# MicroRC-C.net
KiCad netlist of a schematic drawn in EAGLE
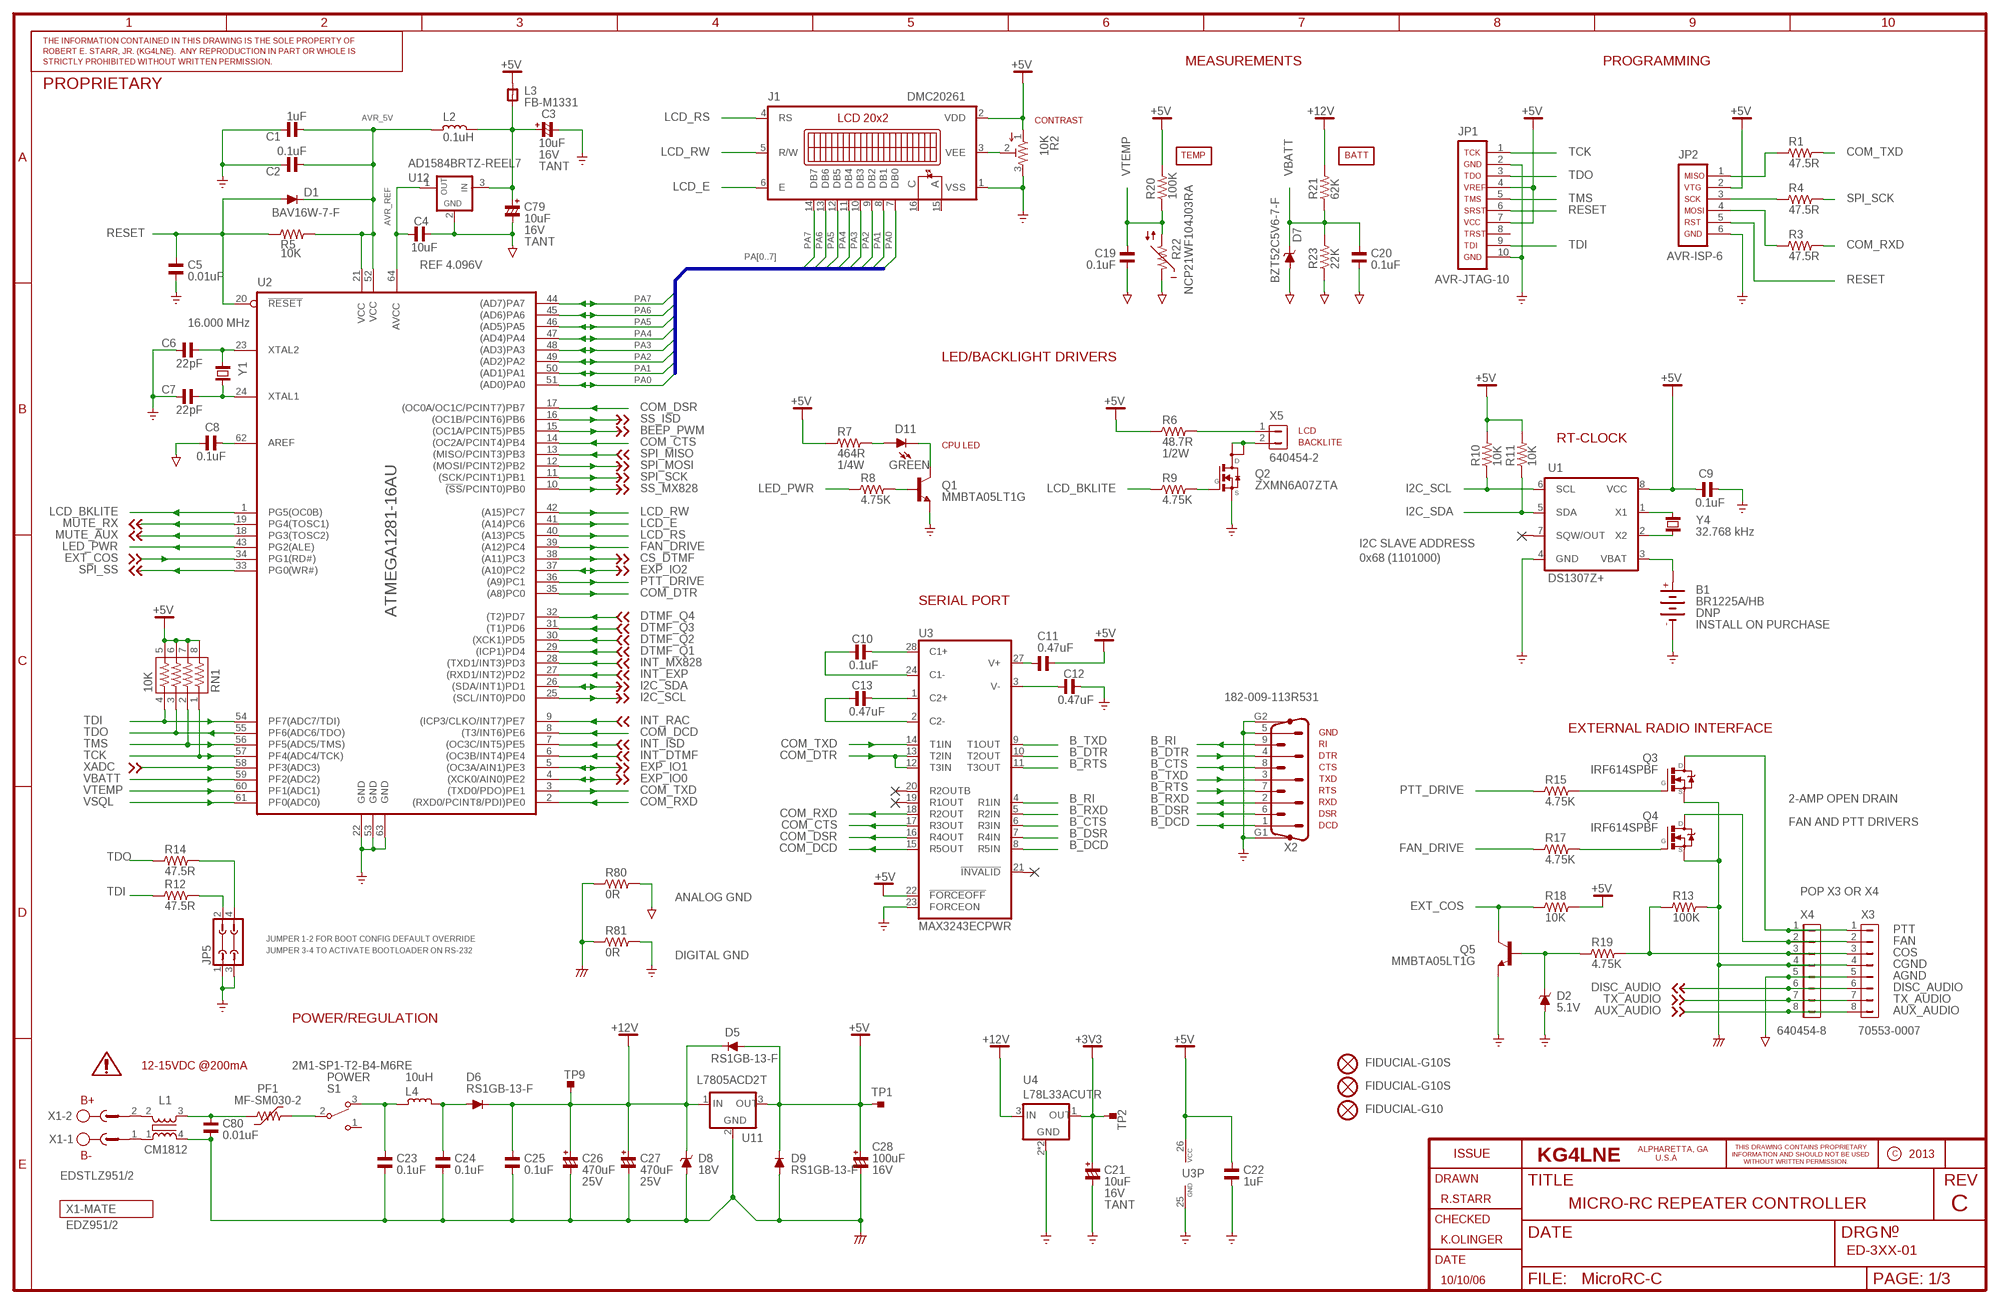
[diagram p0: schematic, sheet 1]
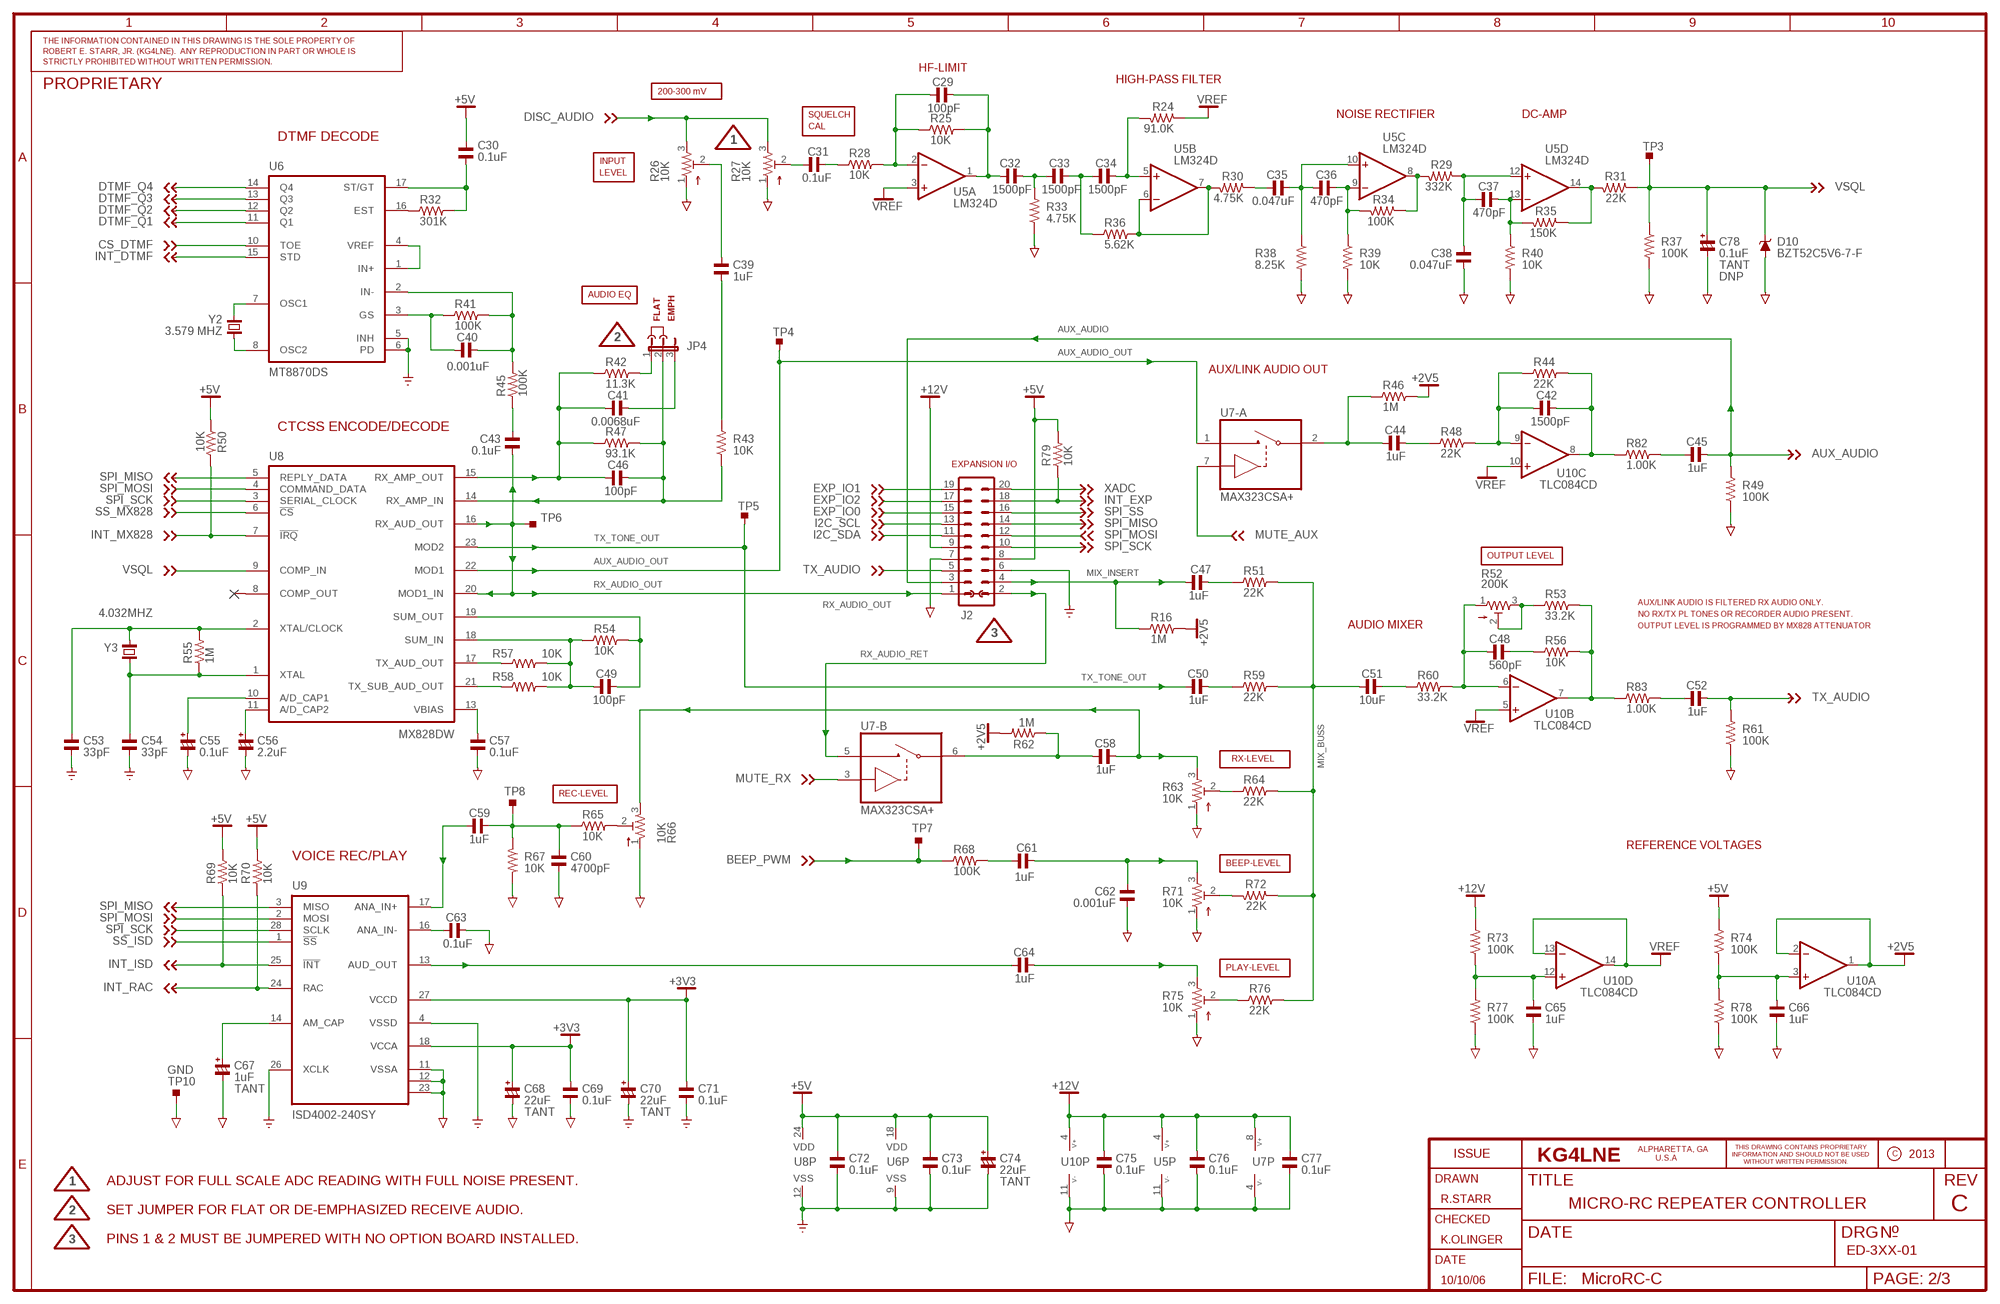
[diagram p1: schematic, sheet 2]
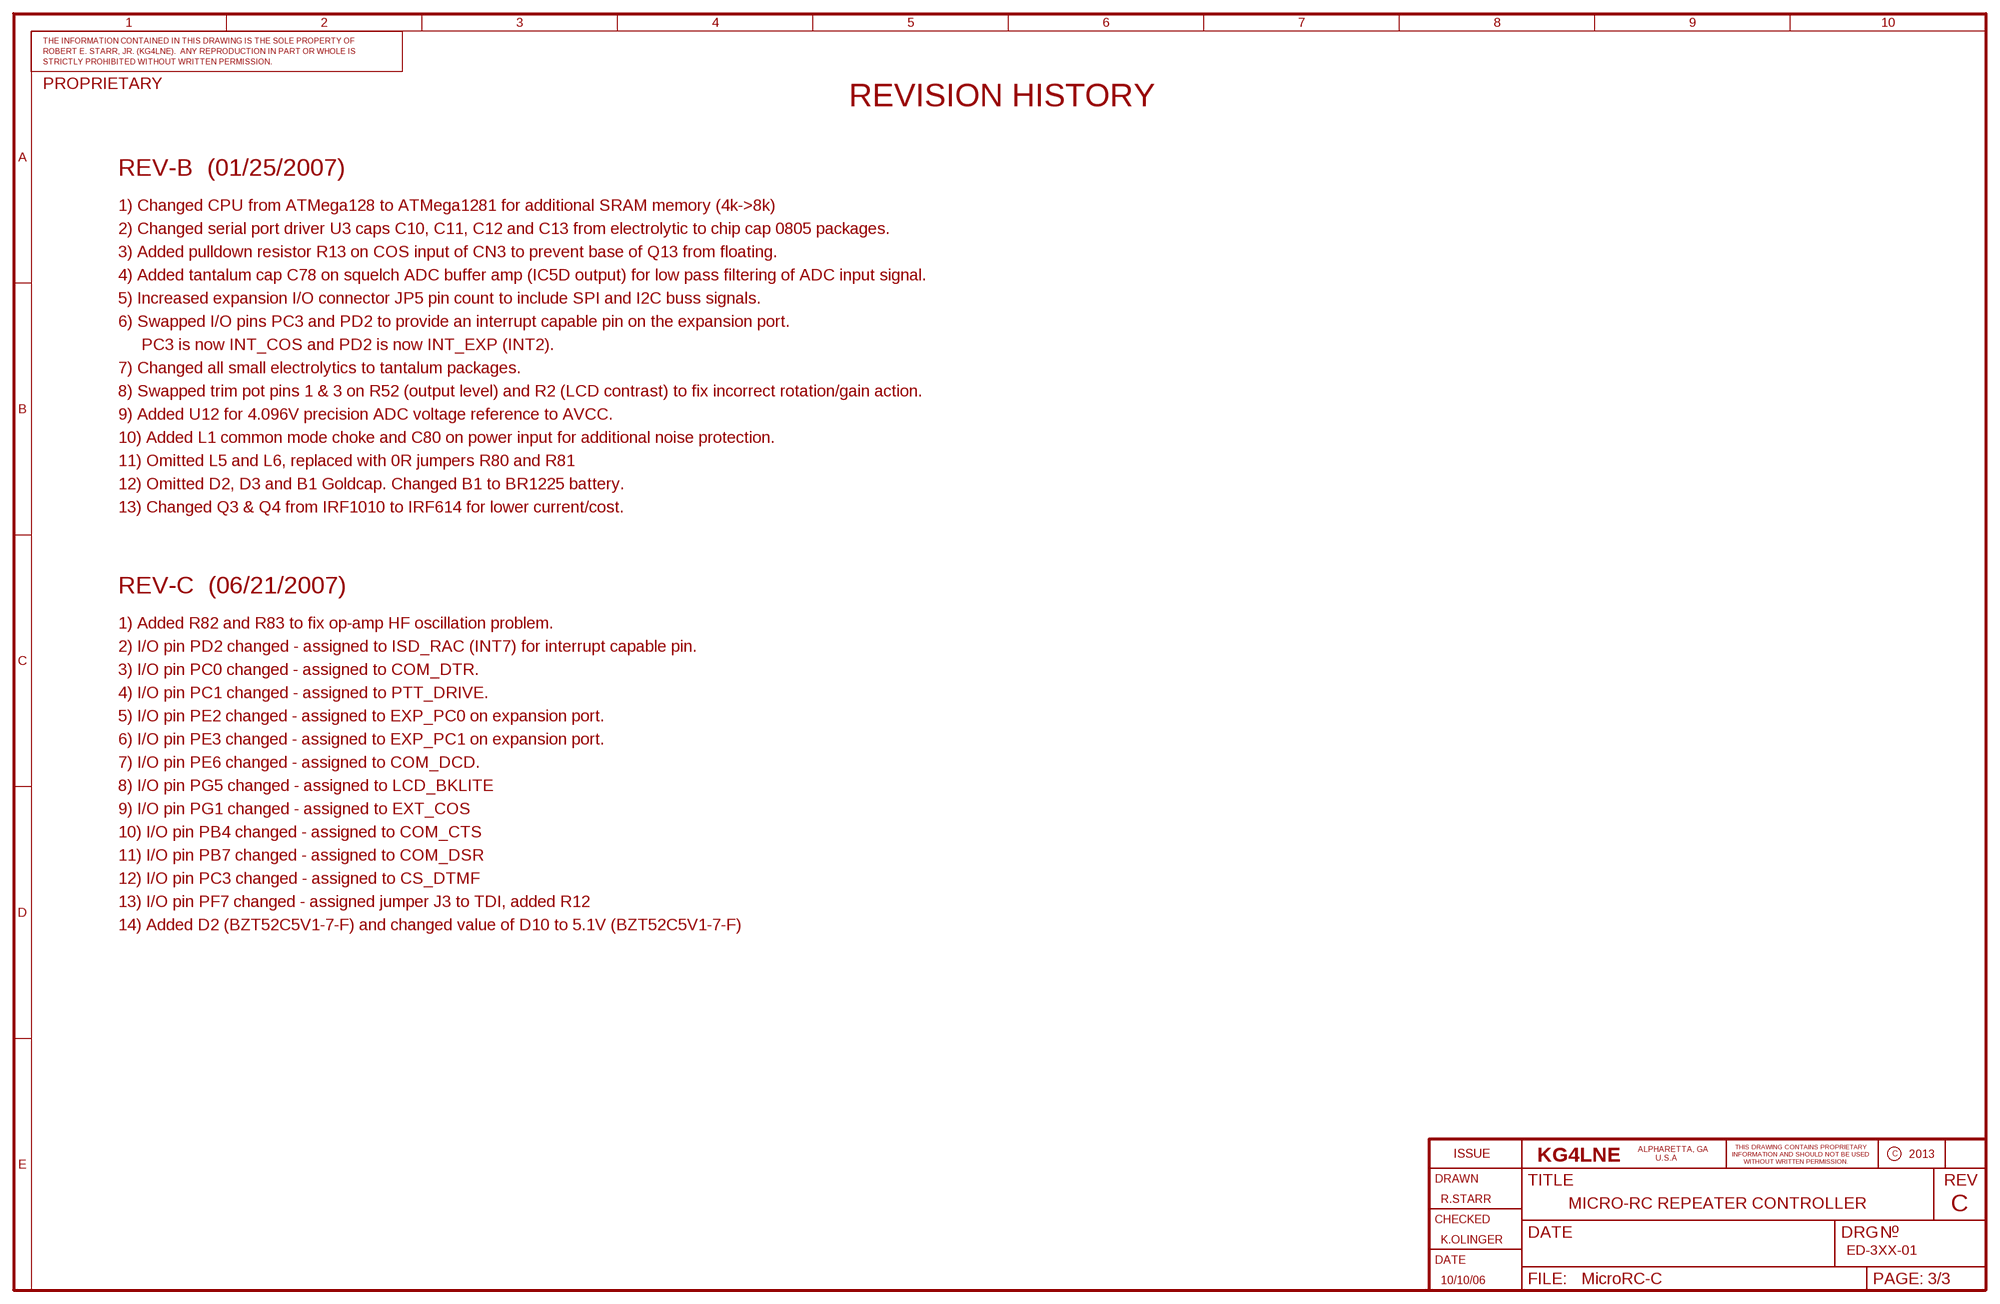
[diagram p2: schematic, sheet 3]

(export (version "E")
  (design (tool "Eeschema 10.0.6"))
  (components
    (comp (ref "B1")
      (value "BR1225A/HB")
      (footprint "eagle-import:BR1225")
      (fields (field (name "PLACE") "INSTALL ON PURCHASE"))
      (libsource (lib "eagle-import") (part "BR1225"))
    )
    (comp (ref "C1")
      (value "1uF")
      (footprint "eagle-import:C0805")
      (fields (field (name "PARTNO") "C0805C105Z3VACTU"))
      (libsource (lib "eagle-import") (part "C_0805"))
    )
    (comp (ref "C2")
      (value "0.1uF")
      (footprint "eagle-import:C0805")
      (fields (field (name "PARTNO") "C0805F104K5RACTU"))
      (libsource (lib "eagle-import") (part "C_0805"))
    )
    (comp (ref "C3")
      (value "10uF")
      (footprint "eagle-import:C3528_T")
      (fields
        (field (name "PARTNO") "T491B106M016AT")
        (field (name "TYPE") "TANT")
        (field (name "VOLT") "16V")
      )
      (libsource (lib "eagle-import") (part "CP_3528"))
    )
    (comp (ref "C4")
      (value "10uF")
      (footprint "eagle-import:C0805")
      (fields (field (name "PARTNO") "C0805C106K9PACTU"))
      (libsource (lib "eagle-import") (part "C_0805"))
    )
    (comp (ref "C5")
      (value "0.01uF")
      (footprint "eagle-import:C0805")
      (fields (field (name "PARTNO") "C0805C103K5RACTU"))
      (libsource (lib "eagle-import") (part "C_0805"))
    )
    (comp (ref "C6")
      (value "22pF")
      (footprint "eagle-import:C0805")
      (fields (field (name "PARTNO") "C0805C220J5GACTU"))
      (libsource (lib "eagle-import") (part "C_0805"))
    )
    (comp (ref "C7")
      (value "22pF")
      (footprint "eagle-import:C0805")
      (fields (field (name "PARTNO") "C0805C220J5GACTU"))
      (libsource (lib "eagle-import") (part "C_0805"))
    )
    (comp (ref "C8")
      (value "0.1uF")
      (footprint "eagle-import:C0805")
      (fields (field (name "PARTNO") "C0805F104K5RACTU"))
      (libsource (lib "eagle-import") (part "C_0805"))
    )
    (comp (ref "C9")
      (value "0.1uF")
      (footprint "eagle-import:C0805")
      (fields (field (name "PARTNO") "C0805F104K5RACTU"))
      (libsource (lib "eagle-import") (part "C_0805"))
    )
    (comp (ref "C10")
      (value "0.1uF")
      (footprint "eagle-import:C0805")
      (fields (field (name "PARTNO") "C0805F104K5RACTU"))
      (libsource (lib "eagle-import") (part "C_0805"))
    )
    (comp (ref "C11")
      (value "0.47uF")
      (footprint "eagle-import:C0805")
      (fields (field (name "PARTNO") "C0805F474K3RACTU"))
      (libsource (lib "eagle-import") (part "C_0805"))
    )
    (comp (ref "C12")
      (value "0.47uF")
      (footprint "eagle-import:C0805")
      (fields (field (name "PARTNO") "C0805F474K3RACTU"))
      (libsource (lib "eagle-import") (part "C_0805"))
    )
    (comp (ref "C13")
      (value "0.47uF")
      (footprint "eagle-import:C0805")
      (fields (field (name "PARTNO") "C0805F474K3RACTU"))
      (libsource (lib "eagle-import") (part "C_0805"))
    )
    (comp (ref "C19")
      (value "0.1uF")
      (footprint "eagle-import:C0805")
      (fields (field (name "PARTNO") "C0805F104K5RACTU"))
      (libsource (lib "eagle-import") (part "C_0805"))
    )
    (comp (ref "C20")
      (value "0.1uF")
      (footprint "eagle-import:C0805")
      (fields (field (name "PARTNO") "C0805F104K5RACTU"))
      (libsource (lib "eagle-import") (part "C_0805"))
    )
    (comp (ref "C21")
      (value "10uF")
      (footprint "eagle-import:C3528_T")
      (fields
        (field (name "PARTNO") "T491B106M016AT")
        (field (name "TYPE") "TANT")
        (field (name "VOLT") "16V")
      )
      (libsource (lib "eagle-import") (part "CP_3528"))
    )
    (comp (ref "C22")
      (value "1uF")
      (footprint "eagle-import:C0805")
      (fields (field (name "PARTNO") "C0805C105Z3VACTU"))
      (libsource (lib "eagle-import") (part "C_0805"))
    )
    (comp (ref "C23")
      (value "0.1uF")
      (footprint "eagle-import:C1206")
      (fields (field (name "PARTNO") "C1206C104K5RACTU"))
      (libsource (lib "eagle-import") (part "C_1206"))
    )
    (comp (ref "C24")
      (value "0.1uF")
      (footprint "eagle-import:C1206")
      (fields (field (name "PARTNO") "C1206C104K5RACTU"))
      (libsource (lib "eagle-import") (part "C_1206"))
    )
    (comp (ref "C25")
      (value "0.1uF")
      (footprint "eagle-import:C1206")
      (fields (field (name "PARTNO") "C1206C104K5RACTU"))
      (libsource (lib "eagle-import") (part "C_1206"))
    )
    (comp (ref "C26")
      (value "470uF")
      (footprint "eagle-import:CSV-G")
      (fields (field (name "PARTNO") "EEE-1EA471P") (field (name "VOLT") "25V"))
      (libsource (lib "eagle-import") (part "CP_SV-G"))
    )
    (comp (ref "C27")
      (value "470uF")
      (footprint "eagle-import:CSV-G")
      (fields (field (name "PARTNO") "EEE-1EA471P") (field (name "VOLT") "25V"))
      (libsource (lib "eagle-import") (part "CP_SV-G"))
    )
    (comp (ref "C28")
      (value "100uF")
      (footprint "eagle-import:CSV-E_F")
      (fields (field (name "PARTNO") "EEE-1CA101P") (field (name "VOLT") "16V"))
      (libsource (lib "eagle-import") (part "CP_SV-E/F"))
    )
    (comp (ref "C79")
      (value "10uF")
      (footprint "eagle-import:C3528_T")
      (fields
        (field (name "PARTNO") "T491B106M016AT")
        (field (name "TYPE") "TANT")
        (field (name "VOLT") "16V")
      )
      (libsource (lib "eagle-import") (part "CP_3528"))
    )
    (comp (ref "C80")
      (value "0.01uF")
      (footprint "eagle-import:C1206")
      (fields (field (name "PARTNO") "12065C103KAT2A"))
      (libsource (lib "eagle-import") (part "C_1206"))
    )
    (comp (ref "D1")
      (value "BAV16W-7-F")
      (footprint "eagle-import:SOD123")
      (libsource (lib "eagle-import") (part "DIODE-SOD123"))
    )
    (comp (ref "D2")
      (value "5.1V")
      (footprint "eagle-import:SOD123")
      (fields (field (name "PARTNO") "BZT52C5V1-7-F"))
      (libsource (lib "eagle-import") (part "ZENER-DIODESOD123"))
    )
    (comp (ref "D5")
      (value "RS1GB-13-F")
      (footprint "eagle-import:SMB")
      (libsource (lib "eagle-import") (part "S1GB-13"))
    )
    (comp (ref "D6")
      (value "RS1GB-13-F")
      (footprint "eagle-import:SMB")
      (libsource (lib "eagle-import") (part "S1GB-13"))
    )
    (comp (ref "D7")
      (value "BZT52C5V6-7-F")
      (footprint "eagle-import:SOD123")
      (libsource (lib "eagle-import") (part "ZENER-DIODESOD123"))
    )
    (comp (ref "D8")
      (value "18V")
      (footprint "eagle-import:SMB")
      (fields (field (name "PARTNO") "1SMB5931BT3G"))
      (libsource (lib "eagle-import") (part "ZENER-DIODESMB"))
    )
    (comp (ref "D9")
      (value "RS1GB-13-F")
      (footprint "eagle-import:SMB")
      (libsource (lib "eagle-import") (part "S1GB-13"))
    )
    (comp (ref "D11")
      (value "GREEN")
      (footprint "eagle-import:LED535")
      (fields (field (name "PARTNO") "5350T5"))
      (libsource (lib "eagle-import") (part "LED535XX"))
    )
    (comp (ref "FIDUCIAL1")
      (value "FIDUCIAL-G10S")
      (footprint "eagle-import:G10S")
      (libsource (lib "eagle-import") (part "FIDUCIAL-G10S"))
    )
    (comp (ref "FIDUCIAL2")
      (value "FIDUCIAL-G10S")
      (footprint "eagle-import:G10S")
      (libsource (lib "eagle-import") (part "FIDUCIAL-G10S"))
    )
    (comp (ref "FIDUCIAL3")
      (value "FIDUCIAL-G10")
      (footprint "eagle-import:G10")
      (libsource (lib "eagle-import") (part "FIDUCIAL-G10"))
    )
    (comp (ref "J1")
      (value "DMC20261")
      (footprint "eagle-import:DMC20261")
      (libsource (lib "eagle-import") (part "DMC20261"))
    )
    (comp (ref "JP1")
      (value "AVR-JTAG-10")
      (footprint "eagle-import:AVR-JTAG-10")
      (libsource (lib "eagle-import") (part "AVR-JTAG-10"))
    )
    (comp (ref "JP2")
      (value "AVR-ISP-6")
      (footprint "eagle-import:AVR-ISP-6")
      (libsource (lib "eagle-import") (part "AVR-ISP-6"))
    )
    (comp (ref "JP5")
      (value "JP2Q")
      (footprint "eagle-import:JP2Q")
      (libsource (lib "eagle-import") (part "JP2Q"))
    )
    (comp (ref "L1")
      (value "CM1812")
      (footprint "eagle-import:CM1812")
      (fields (field (name "PARTNO") "CM1812R600R-10"))
      (libsource (lib "eagle-import") (part "CM1812"))
    )
    (comp (ref "L2")
      (value "0.1uH")
      (footprint "eagle-import:L1206")
      (fields (field (name "PARTNO") "PM1210-R10J"))
      (libsource (lib "eagle-import") (part "L_1206"))
    )
    (comp (ref "L3")
      (value "FB-M1331")
      (footprint "eagle-import:L1206")
      (fields (field (name "PARTNO") "PM2001-200"))
      (libsource (lib "eagle-import") (part "FB_1206"))
    )
    (comp (ref "L4")
      (value "10uH")
      (footprint "eagle-import:PM-13")
      (fields (field (name "PARTNO") "PM3308-100M"))
      (libsource (lib "eagle-import") (part "L-PM3308"))
    )
    (comp (ref "PF1")
      (value "MF-SM030-2")
      (footprint "eagle-import:SMD-7555")
      (libsource (lib "eagle-import") (part "POLYSWITCH-SMD-7555"))
    )
    (comp (ref "Q1")
      (value "MMBTA05LT1G")
      (footprint "eagle-import:SOT23")
      (libsource (lib "eagle-import") (part "MMBTA05LT1"))
    )
    (comp (ref "Q2")
      (value "ZXMN6A07ZTA")
      (footprint "eagle-import:SOT89")
      (libsource (lib "eagle-import") (part "ZXMN6A07Z"))
    )
    (comp (ref "Q3")
      (value "IRF614SPBF")
      (footprint "eagle-import:D2PAK")
      (libsource (lib "eagle-import") (part "IRF614"))
    )
    (comp (ref "Q4")
      (value "IRF614SPBF")
      (footprint "eagle-import:D2PAK")
      (libsource (lib "eagle-import") (part "IRF614"))
    )
    (comp (ref "Q5")
      (value "MMBTA05LT1G")
      (footprint "eagle-import:SOT23")
      (libsource (lib "eagle-import") (part "MMBTA05LT1"))
    )
    (comp (ref "R1")
      (value "47.5R")
      (footprint "eagle-import:R0805")
      (fields (field (name "PARTNO") "ERJ-6ENF47R5V"))
      (libsource (lib "eagle-import") (part "R_0805"))
    )
    (comp (ref "R2")
      (value "10K")
      (footprint "eagle-import:EVM-L4G")
      (fields (field (name "PARTNO") "EVM-L4GA00B14"))
      (libsource (lib "eagle-import") (part "TRIM_EU-EVM-L4G"))
    )
    (comp (ref "R3")
      (value "47.5R")
      (footprint "eagle-import:R0805")
      (fields (field (name "PARTNO") "ERJ-6ENF47R5V"))
      (libsource (lib "eagle-import") (part "R_0805"))
    )
    (comp (ref "R4")
      (value "47.5R")
      (footprint "eagle-import:R0805")
      (fields (field (name "PARTNO") "ERJ-6ENF47R5V"))
      (libsource (lib "eagle-import") (part "R_0805"))
    )
    (comp (ref "R5")
      (value "10K")
      (footprint "eagle-import:R0805")
      (fields (field (name "PARTNO") "ERJ-6ENF1002V"))
      (libsource (lib "eagle-import") (part "R_0805"))
    )
    (comp (ref "R6")
      (value "48.7R")
      (footprint "eagle-import:R2010")
      (fields (field (name "PARTNO") "ERJ-12SF48R7U") (field (name "RATE") "1/2W"))
      (libsource (lib "eagle-import") (part "R_2010"))
    )
    (comp (ref "R7")
      (value "464R")
      (footprint "eagle-import:R1210")
      (fields (field (name "PARTNO") "ERJ-14NF4640U") (field (name "RATE") "1/4W"))
      (libsource (lib "eagle-import") (part "R_1210"))
    )
    (comp (ref "R8")
      (value "4.75K")
      (footprint "eagle-import:R0805")
      (fields (field (name "PARTNO") "ERJ-6ENF4751V"))
      (libsource (lib "eagle-import") (part "R_0805"))
    )
    (comp (ref "R9")
      (value "4.75K")
      (footprint "eagle-import:R0805")
      (fields (field (name "PARTNO") "ERJ-6ENF4751V"))
      (libsource (lib "eagle-import") (part "R_0805"))
    )
    (comp (ref "R10")
      (value "10K")
      (footprint "eagle-import:R0805")
      (fields (field (name "PARTNO") "ERJ-6ENF1002V"))
      (libsource (lib "eagle-import") (part "R_0805"))
    )
    (comp (ref "R11")
      (value "10K")
      (footprint "eagle-import:R0805")
      (fields (field (name "PARTNO") "ERJ-6ENF1002V"))
      (libsource (lib "eagle-import") (part "R_0805"))
    )
    (comp (ref "R12")
      (value "47.5R")
      (footprint "eagle-import:R0805")
      (fields (field (name "PARTNO") "ERJ-6ENF47R5V"))
      (libsource (lib "eagle-import") (part "R_0805"))
    )
    (comp (ref "R13")
      (value "100K")
      (footprint "eagle-import:R0805")
      (fields (field (name "PARTNO") "ERJ-6ENF1003V"))
      (libsource (lib "eagle-import") (part "R_0805"))
    )
    (comp (ref "R14")
      (value "47.5R")
      (footprint "eagle-import:R0805")
      (fields (field (name "PARTNO") "ERJ-6ENF47R5V"))
      (libsource (lib "eagle-import") (part "R_0805"))
    )
    (comp (ref "R15")
      (value "4.75K")
      (footprint "eagle-import:R0805")
      (fields (field (name "PARTNO") "ERJ-6ENF4751V"))
      (libsource (lib "eagle-import") (part "R_0805"))
    )
    (comp (ref "R17")
      (value "4.75K")
      (footprint "eagle-import:R0805")
      (fields (field (name "PARTNO") "ERJ-6ENF4751V"))
      (libsource (lib "eagle-import") (part "R_0805"))
    )
    (comp (ref "R18")
      (value "10K")
      (footprint "eagle-import:R0805")
      (fields (field (name "PARTNO") "ERJ-6ENF1002V"))
      (libsource (lib "eagle-import") (part "R_0805"))
    )
    (comp (ref "R19")
      (value "4.75K")
      (footprint "eagle-import:R0805")
      (fields (field (name "PARTNO") "ERJ-6ENF4751V"))
      (libsource (lib "eagle-import") (part "R_0805"))
    )
    (comp (ref "R20")
      (value "100K")
      (footprint "eagle-import:R0805")
      (fields (field (name "PARTNO") "ERJ-6ENF1003V"))
      (libsource (lib "eagle-import") (part "R_0805"))
    )
    (comp (ref "R21")
      (value "62K")
      (footprint "eagle-import:R0805")
      (fields (field (name "PARTNO") "ERJ-6ENF6192V"))
      (libsource (lib "eagle-import") (part "R_0805"))
    )
    (comp (ref "R22")
      (value "NCP21WF104J03RA")
      (footprint "eagle-import:R0805")
      (libsource (lib "eagle-import") (part "NCP-0805"))
    )
    (comp (ref "R23")
      (value "22K")
      (footprint "eagle-import:R0805")
      (fields (field (name "PARTNO") "ERJ-6ENF2212V"))
      (libsource (lib "eagle-import") (part "R_0805"))
    )
    (comp (ref "R80")
      (value "0R")
      (footprint "eagle-import:R0805")
      (fields (field (name "PARTNO") "RC0805JR-070RL"))
      (libsource (lib "eagle-import") (part "R_0805"))
    )
    (comp (ref "R81")
      (value "0R")
      (footprint "eagle-import:R0805")
      (fields (field (name "PARTNO") "RC0805JR-070RL"))
      (libsource (lib "eagle-import") (part "R_0805"))
    )
    (comp (ref "RN1")
      (value "10K")
      (footprint "eagle-import:744-8")
      (fields (field (name "PARTNO") "744C083103JPTR"))
      (libsource (lib "eagle-import") (part "744-8"))
    )
    (comp (ref "S1")
      (value "2M1-SP1-T2-B4-M6RE")
      (footprint "eagle-import:CK-A")
      (libsource (lib "eagle-import") (part "CK-A"))
    )
    (comp (ref "TP1")
      (value "TPTP10SQ")
      (footprint "eagle-import:TP10SQ")
      (libsource (lib "eagle-import") (part "TPTP10SQ"))
    )
    (comp (ref "TP2")
      (value "TPTP10SQ")
      (footprint "eagle-import:TP10SQ")
      (libsource (lib "eagle-import") (part "TPTP10SQ"))
    )
    (comp (ref "TP9")
      (value "TPTP10SQ")
      (footprint "eagle-import:TP10SQ")
      (libsource (lib "eagle-import") (part "TPTP10SQ"))
    )
    (comp (ref "U1")
      (value "DS1307Z+")
      (footprint "eagle-import:SO08")
      (libsource (lib "eagle-import") (part "DS1307Z"))
    )
    (comp (ref "U2")
      (value "ATMEGA1281-16AU")
      (footprint "eagle-import:TQFP64-AEB")
      (libsource (lib "eagle-import") (part "MEGA1281/2561"))
    )
    (comp (ref "U3")
      (value "MAX3243ECPWR")
      (footprint "eagle-import:TSSOP28")
      (fields (field (name "PARTNO") "MAX3243ECPWR"))
      (libsource (lib "eagle-import") (part "MAX3243PW"))
    )
    (comp (ref "U4")
      (value "L78L33ACUTR")
      (footprint "eagle-import:SOT89-4")
      (libsource (lib "eagle-import") (part "L78LXXCU/BU"))
    )
    (comp (ref "U11")
      (value "L7805ACD2T")
      (footprint "eagle-import:D2PAK")
      (libsource (lib "eagle-import") (part "L78XXD2T"))
    )
    (comp (ref "U12")
      (value "AD1584BRTZ-REEL7")
      (footprint "eagle-import:SOT23")
      (libsource (lib "eagle-import") (part "AD158X"))
    )
    (comp (ref "X1")
      (value "EDSTLZ951/2")
      (footprint "eagle-import:951-2")
      (fields (field (name "PARTNO") "EDSTLZ951/2"))
      (libsource (lib "eagle-import") (part "EDSTLZ-2-951"))
    )
    (comp (ref "X2")
      (value "182-009-113R531")
      (footprint "eagle-import:NC182M9")
      (libsource (lib "eagle-import") (part "NC182M9-VS"))
    )
    (comp (ref "X3")
      (value "70553-0007")
      (footprint "eagle-import:70553-08")
      (fields (field (name "PLACE") "POP X3 OR X4"))
      (libsource (lib "eagle-import") (part "HDR-1X8-70553-?"))
    )
    (comp (ref "X4")
      (value "640454-8")
      (footprint "eagle-import:MTA08-100")
      (libsource (lib "eagle-import") (part "MTA08-100"))
    )
    (comp (ref "X5")
      (value "640454-2")
      (footprint "eagle-import:MTA-100-2V")
      (libsource (lib "eagle-import") (part "HDR-1X2-MTA-100"))
    )
    (comp (ref "Y1")
      (value "16.000 MHz")
      (footprint "eagle-import:TC38H")
      (fields (field (name "PARTNO") "ECS-160-18-9X"))
      (libsource (lib "eagle-import") (part "CRYTALTC38H"))
    )
    (comp (ref "Y4")
      (value "32.768 kHz")
      (footprint "eagle-import:TC26H")
      (fields (field (name "PARTNO") "ECS-.327-12.5-13X"))
      (libsource (lib "eagle-import") (part "CRYTALTC26H"))
    )
    (comp (ref "C29")
      (value "100pF")
      (footprint "eagle-import:C0805")
      (fields (field (name "PARTNO") "C0805C101J5GACTU"))
      (libsource (lib "eagle-import") (part "C_0805"))
    )
    (comp (ref "C30")
      (value "0.1uF")
      (footprint "eagle-import:C0805")
      (fields (field (name "PARTNO") "C0805F104K5RACTU"))
      (libsource (lib "eagle-import") (part "C_0805"))
    )
    (comp (ref "C31")
      (value "0.1uF")
      (footprint "eagle-import:C0805")
      (fields (field (name "PARTNO") "C0805F104K5RACTU"))
      (libsource (lib "eagle-import") (part "C_0805"))
    )
    (comp (ref "C32")
      (value "1500pF")
      (footprint "eagle-import:C0805")
      (fields (field (name "PARTNO") "C0805C152K5RACTU"))
      (libsource (lib "eagle-import") (part "C_0805"))
    )
    (comp (ref "C33")
      (value "1500pF")
      (footprint "eagle-import:C0805")
      (fields (field (name "PARTNO") "C0805C152K5RACTU"))
      (libsource (lib "eagle-import") (part "C_0805"))
    )
    (comp (ref "C34")
      (value "1500pF")
      (footprint "eagle-import:C0805")
      (fields (field (name "PARTNO") "C0805C152K5RACTU"))
      (libsource (lib "eagle-import") (part "C_0805"))
    )
    (comp (ref "C35")
      (value "0.047uF")
      (footprint "eagle-import:C0805")
      (fields (field (name "PARTNO") "C0805C473K5RACTU"))
      (libsource (lib "eagle-import") (part "C_0805"))
    )
    (comp (ref "C36")
      (value "470pF")
      (footprint "eagle-import:C0805")
      (fields (field (name "PARTNO") "C0805C471J5GACTU"))
      (libsource (lib "eagle-import") (part "C_0805"))
    )
    (comp (ref "C37")
      (value "470pF")
      (footprint "eagle-import:C0805")
      (fields (field (name "PARTNO") "C0805C471J5GACTU"))
      (libsource (lib "eagle-import") (part "C_0805"))
    )
    (comp (ref "C38")
      (value "0.047uF")
      (footprint "eagle-import:C0805")
      (fields (field (name "PARTNO") "C0805C473K5RACTU"))
      (libsource (lib "eagle-import") (part "C_0805"))
    )
    (comp (ref "C39")
      (value "1uF")
      (footprint "eagle-import:C0805")
      (fields (field (name "PARTNO") "C0805C105Z3VACTU"))
      (libsource (lib "eagle-import") (part "C_0805"))
    )
    (comp (ref "C40")
      (value "0.001uF")
      (footprint "eagle-import:C0805")
      (fields (field (name "PARTNO") "C0805C102K5RACTU"))
      (libsource (lib "eagle-import") (part "C_0805"))
    )
    (comp (ref "C41")
      (value "0.0068uF")
      (footprint "eagle-import:C0805")
      (fields (field (name "PARTNO") "C0805C682K5RACTU"))
      (libsource (lib "eagle-import") (part "C_0805"))
    )
    (comp (ref "C42")
      (value "1500pF")
      (footprint "eagle-import:C0805")
      (fields (field (name "PARTNO") "C0805C152K5RACTU"))
      (libsource (lib "eagle-import") (part "C_0805"))
    )
    (comp (ref "C43")
      (value "0.1uF")
      (footprint "eagle-import:C0805")
      (fields (field (name "PARTNO") "C0805F104K5RACTU"))
      (libsource (lib "eagle-import") (part "C_0805"))
    )
    (comp (ref "C44")
      (value "1uF")
      (footprint "eagle-import:C0805")
      (fields (field (name "PARTNO") "C0805C105Z3VACTU"))
      (libsource (lib "eagle-import") (part "C_0805"))
    )
    (comp (ref "C45")
      (value "1uF")
      (footprint "eagle-import:C0805")
      (fields (field (name "PARTNO") "C0805C105Z3VACTU"))
      (libsource (lib "eagle-import") (part "C_0805"))
    )
    (comp (ref "C46")
      (value "100pF")
      (footprint "eagle-import:C0805")
      (fields (field (name "PARTNO") "C0805C101J5GACTU"))
      (libsource (lib "eagle-import") (part "C_0805"))
    )
    (comp (ref "C47")
      (value "1uF")
      (footprint "eagle-import:C0805")
      (fields (field (name "PARTNO") "C0805C105Z3VACTU"))
      (libsource (lib "eagle-import") (part "C_0805"))
    )
    (comp (ref "C48")
      (value "560pF")
      (footprint "eagle-import:C0805")
      (fields (field (name "PARTNO") "C0805C561J5GACTU"))
      (libsource (lib "eagle-import") (part "C_0805"))
    )
    (comp (ref "C49")
      (value "100pF")
      (footprint "eagle-import:C0805")
      (fields (field (name "PARTNO") "C0805C101J5GACTU"))
      (libsource (lib "eagle-import") (part "C_0805"))
    )
    (comp (ref "C50")
      (value "1uF")
      (footprint "eagle-import:C0805")
      (fields (field (name "PARTNO") "C0805C105Z3VACTU"))
      (libsource (lib "eagle-import") (part "C_0805"))
    )
    (comp (ref "C51")
      (value "10uF")
      (footprint "eagle-import:C0805")
      (fields (field (name "PARTNO") "C0805C106K9PACTU"))
      (libsource (lib "eagle-import") (part "C_0805"))
    )
    (comp (ref "C52")
      (value "1uF")
      (footprint "eagle-import:C0805")
      (fields (field (name "PARTNO") "C0805C105Z3VACTU"))
      (libsource (lib "eagle-import") (part "C_0805"))
    )
    (comp (ref "C53")
      (value "33pF")
      (footprint "eagle-import:C0805")
      (fields (field (name "PARTNO") "C0805C330J5GACTU"))
      (libsource (lib "eagle-import") (part "C_0805"))
    )
    (comp (ref "C54")
      (value "33pF")
      (footprint "eagle-import:C0805")
      (fields (field (name "PARTNO") "C0805C330J5GACTU"))
      (libsource (lib "eagle-import") (part "C_0805"))
    )
    (comp (ref "C55")
      (value "0.1uF")
      (footprint "eagle-import:C3216_T")
      (fields (field (name "PARTNO") "T491A104K035AT"))
      (libsource (lib "eagle-import") (part "CP_3216"))
    )
    (comp (ref "C56")
      (value "2.2uF")
      (footprint "eagle-import:C3216_T")
      (fields (field (name "PARTNO") "T491A225K010AT"))
      (libsource (lib "eagle-import") (part "CP_3216"))
    )
    (comp (ref "C57")
      (value "0.1uF")
      (footprint "eagle-import:C0805")
      (fields (field (name "PARTNO") "C0805F104K5RACTU"))
      (libsource (lib "eagle-import") (part "C_0805"))
    )
    (comp (ref "C58")
      (value "1uF")
      (footprint "eagle-import:C0805")
      (fields (field (name "PARTNO") "C0805C105Z3VACTU"))
      (libsource (lib "eagle-import") (part "C_0805"))
    )
    (comp (ref "C59")
      (value "1uF")
      (footprint "eagle-import:C0805")
      (fields (field (name "PARTNO") "C0805C105Z3VACTU"))
      (libsource (lib "eagle-import") (part "C_0805"))
    )
    (comp (ref "C60")
      (value "4700pF")
      (footprint "eagle-import:C0805")
      (fields (field (name "PARTNO") "C0805C472K5RACTU"))
      (libsource (lib "eagle-import") (part "C_0805"))
    )
    (comp (ref "C61")
      (value "1uF")
      (footprint "eagle-import:C0805")
      (fields (field (name "PARTNO") "C0805C105Z3VACTU"))
      (libsource (lib "eagle-import") (part "C_0805"))
    )
    (comp (ref "C62")
      (value "0.001uF")
      (footprint "eagle-import:C0805")
      (fields (field (name "PARTNO") "C0805C102K5RACTU"))
      (libsource (lib "eagle-import") (part "C_0805"))
    )
    (comp (ref "C63")
      (value "0.1uF")
      (footprint "eagle-import:C0805")
      (fields (field (name "PARTNO") "C0805F104K5RACTU"))
      (libsource (lib "eagle-import") (part "C_0805"))
    )
    (comp (ref "C64")
      (value "1uF")
      (footprint "eagle-import:C0805")
      (fields (field (name "PARTNO") "C0805C105Z3VACTU"))
      (libsource (lib "eagle-import") (part "C_0805"))
    )
    (comp (ref "C65")
      (value "1uF")
      (footprint "eagle-import:C0805")
      (fields (field (name "PARTNO") "C0805C105Z3VACTU"))
      (libsource (lib "eagle-import") (part "C_0805"))
    )
    (comp (ref "C66")
      (value "1uF")
      (footprint "eagle-import:C0805")
      (fields (field (name "PARTNO") "C0805C105Z3VACTU"))
      (libsource (lib "eagle-import") (part "C_0805"))
    )
    (comp (ref "C67")
      (value "1uF")
      (footprint "eagle-import:C3216_T")
      (fields (field (name "PARTNO") "T491A105K016AT") (field (name "TYPE") "TANT"))
      (libsource (lib "eagle-import") (part "CP_3216"))
    )
    (comp (ref "C68")
      (value "22uF")
      (footprint "eagle-import:C3528_T")
      (fields (field (name "PARTNO") "T491B226M016AT") (field (name "TYPE") "TANT"))
      (libsource (lib "eagle-import") (part "CP_3528"))
    )
    (comp (ref "C69")
      (value "0.1uF")
      (footprint "eagle-import:C0805")
      (fields (field (name "PARTNO") "C0805F104K5RACTU"))
      (libsource (lib "eagle-import") (part "C_0805"))
    )
    (comp (ref "C70")
      (value "22uF")
      (footprint "eagle-import:C3528_T")
      (fields (field (name "PARTNO") "T491B226M016AT") (field (name "TYPE") "TANT"))
      (libsource (lib "eagle-import") (part "CP_3528"))
    )
    (comp (ref "C71")
      (value "0.1uF")
      (footprint "eagle-import:C0805")
      (fields (field (name "PARTNO") "C0805F104K5RACTU"))
      (libsource (lib "eagle-import") (part "C_0805"))
    )
    (comp (ref "C72")
      (value "0.1uF")
      (footprint "eagle-import:C0805")
      (fields (field (name "PARTNO") "C0805F104K5RACTU"))
      (libsource (lib "eagle-import") (part "C_0805"))
    )
    (comp (ref "C73")
      (value "0.1uF")
      (footprint "eagle-import:C0805")
      (fields (field (name "PARTNO") "C0805F104K5RACTU"))
      (libsource (lib "eagle-import") (part "C_0805"))
    )
    (comp (ref "C74")
      (value "22uF")
      (footprint "eagle-import:C3528_T")
      (fields (field (name "PARTNO") "T491B226M016AT") (field (name "TYPE") "TANT"))
      (libsource (lib "eagle-import") (part "CP_3528"))
    )
    (comp (ref "C75")
      (value "0.1uF")
      (footprint "eagle-import:C0805")
      (fields (field (name "PARTNO") "C0805F104K5RACTU"))
      (libsource (lib "eagle-import") (part "C_0805"))
    )
    (comp (ref "C76")
      (value "0.1uF")
      (footprint "eagle-import:C0805")
      (fields (field (name "PARTNO") "C0805F104K5RACTU"))
      (libsource (lib "eagle-import") (part "C_0805"))
    )
    (comp (ref "C77")
      (value "0.1uF")
      (footprint "eagle-import:C0805")
      (fields (field (name "PARTNO") "C0805F104K5RACTU"))
      (libsource (lib "eagle-import") (part "C_0805"))
    )
    (comp (ref "C78")
      (value "0.1uF")
      (footprint "eagle-import:C3216_T")
      (fields (field (name "PARTNO") "DNP") (field (name "TYPE") "TANT"))
      (libsource (lib "eagle-import") (part "CP_3216"))
    )
    (comp (ref "D10")
      (value "BZT52C5V6-7-F")
      (footprint "eagle-import:SOD123")
      (libsource (lib "eagle-import") (part "ZENER-DIODESOD123"))
    )
    (comp (ref "J2")
      (value "MA10-2")
      (footprint "eagle-import:MA10-2")
      (libsource (lib "eagle-import") (part "MA10-2"))
    )
    (comp (ref "JP4")
      (value "JP2E")
      (footprint "eagle-import:JP2")
      (libsource (lib "eagle-import") (part "JP2E"))
    )
    (comp (ref "R16")
      (value "1M")
      (footprint "eagle-import:R0805")
      (fields (field (name "PARTNO") "ERJ-6ENF1004V"))
      (libsource (lib "eagle-import") (part "R_0805"))
    )
    (comp (ref "R24")
      (value "91.0K")
      (footprint "eagle-import:R0805")
      (fields (field (name "PARTNO") "ERJ-6ENF9092V"))
      (libsource (lib "eagle-import") (part "R_0805"))
    )
    (comp (ref "R25")
      (value "10K")
      (footprint "eagle-import:R0805")
      (fields (field (name "PARTNO") "ERJ-6ENF1002V"))
      (libsource (lib "eagle-import") (part "R_0805"))
    )
    (comp (ref "R26")
      (value "10K")
      (footprint "eagle-import:EVME-SIDE")
      (fields (field (name "PARTNO") "EVM-EGGA00B14"))
      (libsource (lib "eagle-import") (part "TRIM_EU-EVME-SIDE"))
    )
    (comp (ref "R27")
      (value "10K")
      (footprint "eagle-import:EVME-SIDE")
      (fields (field (name "PARTNO") "EVM-EGGA00B14"))
      (libsource (lib "eagle-import") (part "TRIM_EU-EVME-SIDE"))
    )
    (comp (ref "R28")
      (value "10K")
      (footprint "eagle-import:R0805")
      (fields (field (name "PARTNO") "ERJ-6ENF1002V"))
      (libsource (lib "eagle-import") (part "R_0805"))
    )
    (comp (ref "R29")
      (value "332K")
      (footprint "eagle-import:R0805")
      (fields (field (name "PARTNO") "ERJ-6ENF3323V"))
      (libsource (lib "eagle-import") (part "R_0805"))
    )
    (comp (ref "R30")
      (value "4.75K")
      (footprint "eagle-import:R0805")
      (fields (field (name "PARTNO") "ERJ-6ENF4751V"))
      (libsource (lib "eagle-import") (part "R_0805"))
    )
    (comp (ref "R31")
      (value "22K")
      (footprint "eagle-import:R0805")
      (fields (field (name "PARTNO") "ERJ-6ENF2212V"))
      (libsource (lib "eagle-import") (part "R_0805"))
    )
    (comp (ref "R32")
      (value "301K")
      (footprint "eagle-import:R0805")
      (fields (field (name "PARTNO") "ERJ-6ENF3013V"))
      (libsource (lib "eagle-import") (part "R_0805"))
    )
    (comp (ref "R33")
      (value "4.75K")
      (footprint "eagle-import:R0805")
      (fields (field (name "PARTNO") "ERJ-6ENF4751V"))
      (libsource (lib "eagle-import") (part "R_0805"))
    )
    (comp (ref "R34")
      (value "100K")
      (footprint "eagle-import:R0805")
      (fields (field (name "PARTNO") "ERJ-6ENF1003V"))
      (libsource (lib "eagle-import") (part "R_0805"))
    )
    (comp (ref "R35")
      (value "150K")
      (footprint "eagle-import:R0805")
      (fields (field (name "PARTNO") "ERJ-6ENF1503V"))
      (libsource (lib "eagle-import") (part "R_0805"))
    )
    (comp (ref "R36")
      (value "5.62K")
      (footprint "eagle-import:R0805")
      (fields (field (name "PARTNO") "ERJ-6ENF5621V"))
      (libsource (lib "eagle-import") (part "R_0805"))
    )
    (comp (ref "R37")
      (value "100K")
      (footprint "eagle-import:R0805")
      (fields (field (name "PARTNO") "ERJ-6ENF1003V"))
      (libsource (lib "eagle-import") (part "R_0805"))
    )
    (comp (ref "R38")
      (value "8.25K")
      (footprint "eagle-import:R0805")
      (fields (field (name "PARTNO") "ERJ-6ENF8251V"))
      (libsource (lib "eagle-import") (part "R_0805"))
    )
    (comp (ref "R39")
      (value "10K")
      (footprint "eagle-import:R0805")
      (fields (field (name "PARTNO") "ERJ-6ENF1002V"))
      (libsource (lib "eagle-import") (part "R_0805"))
    )
    (comp (ref "R40")
      (value "10K")
      (footprint "eagle-import:R0805")
      (fields (field (name "PARTNO") "ERJ-6ENF1002V"))
      (libsource (lib "eagle-import") (part "R_0805"))
    )
    (comp (ref "R41")
      (value "100K")
      (footprint "eagle-import:R0805")
      (fields (field (name "PARTNO") "ERJ-6ENF1003V"))
      (libsource (lib "eagle-import") (part "R_0805"))
    )
    (comp (ref "R42")
      (value "11.3K")
      (footprint "eagle-import:R0805")
      (fields (field (name "PARTNO") "ERJ-6ENF1132V"))
      (libsource (lib "eagle-import") (part "R_0805"))
    )
    (comp (ref "R43")
      (value "10K")
      (footprint "eagle-import:R0805")
      (fields (field (name "PARTNO") "ERJ-6ENF1002V"))
      (libsource (lib "eagle-import") (part "R_0805"))
    )
    (comp (ref "R44")
      (value "22K")
      (footprint "eagle-import:R0805")
      (fields (field (name "PARTNO") "ERJ-6ENF2212V"))
      (libsource (lib "eagle-import") (part "R_0805"))
    )
    (comp (ref "R45")
      (value "100K")
      (footprint "eagle-import:R0805")
      (fields (field (name "PARTNO") "ERJ-6ENF1003V"))
      (libsource (lib "eagle-import") (part "R_0805"))
    )
    (comp (ref "R46")
      (value "1M")
      (footprint "eagle-import:R0805")
      (fields (field (name "PARTNO") "ERJ-6ENF1004V"))
      (libsource (lib "eagle-import") (part "R_0805"))
    )
    (comp (ref "R47")
      (value "93.1K")
      (footprint "eagle-import:R0805")
      (fields (field (name "PARTNO") "ERJ-6ENF9312V"))
      (libsource (lib "eagle-import") (part "R_0805"))
    )
    (comp (ref "R48")
      (value "22K")
      (footprint "eagle-import:R0805")
      (fields (field (name "PARTNO") "ERJ-6ENF2212V"))
      (libsource (lib "eagle-import") (part "R_0805"))
    )
    (comp (ref "R49")
      (value "100K")
      (footprint "eagle-import:R0805")
      (fields (field (name "PARTNO") "ERJ-6ENF1003V"))
      (libsource (lib "eagle-import") (part "R_0805"))
    )
    (comp (ref "R50")
      (value "10K")
      (footprint "eagle-import:R0805")
      (fields (field (name "PARTNO") "ERJ-6ENF1002V"))
      (libsource (lib "eagle-import") (part "R_0805"))
    )
    (comp (ref "R51")
      (value "22K")
      (footprint "eagle-import:R0805")
      (fields (field (name "PARTNO") "ERJ-6ENF2212V"))
      (libsource (lib "eagle-import") (part "R_0805"))
    )
    (comp (ref "R52")
      (value "200K")
      (footprint "eagle-import:EVME-SIDE")
      (fields (field (name "PARTNO") "EVM-EGGA00B25"))
      (libsource (lib "eagle-import") (part "TRIM_EU-EVME-SIDE"))
    )
    (comp (ref "R53")
      (value "33.2K")
      (footprint "eagle-import:R0805")
      (fields (field (name "PARTNO") "ERJ-6ENF3322V"))
      (libsource (lib "eagle-import") (part "R_0805"))
    )
    (comp (ref "R54")
      (value "10K")
      (footprint "eagle-import:R0805")
      (fields (field (name "PARTNO") "ERJ-6ENF1002V"))
      (libsource (lib "eagle-import") (part "R_0805"))
    )
    (comp (ref "R55")
      (value "1M")
      (footprint "eagle-import:R0805")
      (fields (field (name "PARTNO") "ERJ-6ENF1004V"))
      (libsource (lib "eagle-import") (part "R_0805"))
    )
    (comp (ref "R56")
      (value "10K")
      (footprint "eagle-import:R0805")
      (fields (field (name "PARTNO") "ERJ-6ENF1002V"))
      (libsource (lib "eagle-import") (part "R_0805"))
    )
    (comp (ref "R57")
      (value "10K")
      (footprint "eagle-import:R0805")
      (fields (field (name "PARTNO") "ERJ-6ENF1002V"))
      (libsource (lib "eagle-import") (part "R_0805"))
    )
    (comp (ref "R58")
      (value "10K")
      (footprint "eagle-import:R0805")
      (fields (field (name "PARTNO") "ERJ-6ENF1002V"))
      (libsource (lib "eagle-import") (part "R_0805"))
    )
    (comp (ref "R59")
      (value "22K")
      (footprint "eagle-import:R0805")
      (fields (field (name "PARTNO") "ERJ-6ENF2212V"))
      (libsource (lib "eagle-import") (part "R_0805"))
    )
    (comp (ref "R60")
      (value "33.2K")
      (footprint "eagle-import:R0805")
      (fields (field (name "PARTNO") "ERJ-6ENF3322V"))
      (libsource (lib "eagle-import") (part "R_0805"))
    )
    (comp (ref "R61")
      (value "100K")
      (footprint "eagle-import:R0805")
      (fields (field (name "PARTNO") "ERJ-6ENF1003V"))
      (libsource (lib "eagle-import") (part "R_0805"))
    )
    (comp (ref "R62")
      (value "1M")
      (footprint "eagle-import:R0805")
      (fields (field (name "PARTNO") "ERJ-6ENF1004V"))
      (libsource (lib "eagle-import") (part "R_0805"))
    )
    (comp (ref "R63")
      (value "10K")
      (footprint "eagle-import:EVME-SIDE")
      (fields (field (name "PARTNO") "EVM-EGGA00B14"))
      (libsource (lib "eagle-import") (part "TRIM_EU-EVME-SIDE"))
    )
    (comp (ref "R64")
      (value "22K")
      (footprint "eagle-import:R0805")
      (fields (field (name "PARTNO") "ERJ-6ENF2212V"))
      (libsource (lib "eagle-import") (part "R_0805"))
    )
    (comp (ref "R65")
      (value "10K")
      (footprint "eagle-import:R0805")
      (fields (field (name "PARTNO") "ERJ-6ENF1002V"))
      (libsource (lib "eagle-import") (part "R_0805"))
    )
    (comp (ref "R66")
      (value "10K")
      (footprint "eagle-import:EVM-L4G")
      (fields (field (name "PARTNO") "EVM-L4GA00B14"))
      (libsource (lib "eagle-import") (part "TRIM_EU-EVM-L4G"))
    )
    (comp (ref "R67")
      (value "10K")
      (footprint "eagle-import:R0805")
      (fields (field (name "PARTNO") "ERJ-6ENF1002V"))
      (libsource (lib "eagle-import") (part "R_0805"))
    )
    (comp (ref "R68")
      (value "100K")
      (footprint "eagle-import:R0805")
      (fields (field (name "PARTNO") "ERJ-6ENF1003V"))
      (libsource (lib "eagle-import") (part "R_0805"))
    )
    (comp (ref "R69")
      (value "10K")
      (footprint "eagle-import:R0805")
      (fields (field (name "PARTNO") "ERJ-6ENF1002V"))
      (libsource (lib "eagle-import") (part "R_0805"))
    )
    (comp (ref "R70")
      (value "10K")
      (footprint "eagle-import:R0805")
      (fields (field (name "PARTNO") "ERJ-6ENF1002V"))
      (libsource (lib "eagle-import") (part "R_0805"))
    )
    (comp (ref "R71")
      (value "10K")
      (footprint "eagle-import:EVME-SIDE")
      (fields (field (name "PARTNO") "EVM-EGGA00B14"))
      (libsource (lib "eagle-import") (part "TRIM_EU-EVME-SIDE"))
    )
    (comp (ref "R72")
      (value "22K")
      (footprint "eagle-import:R0805")
      (fields (field (name "PARTNO") "ERJ-6ENF2212V"))
      (libsource (lib "eagle-import") (part "R_0805"))
    )
    (comp (ref "R73")
      (value "100K")
      (footprint "eagle-import:R0805")
      (fields (field (name "PARTNO") "ERJ-6ENF1003V"))
      (libsource (lib "eagle-import") (part "R_0805"))
    )
    (comp (ref "R74")
      (value "100K")
      (footprint "eagle-import:R0805")
      (fields (field (name "PARTNO") "ERJ-6ENF1003V"))
      (libsource (lib "eagle-import") (part "R_0805"))
    )
    (comp (ref "R75")
      (value "10K")
      (footprint "eagle-import:EVME-SIDE")
      (fields (field (name "PARTNO") "EVM-EGGA00B14"))
      (libsource (lib "eagle-import") (part "TRIM_EU-EVME-SIDE"))
    )
    (comp (ref "R76")
      (value "22K")
      (footprint "eagle-import:R0805")
      (fields (field (name "PARTNO") "ERJ-6ENF2212V"))
      (libsource (lib "eagle-import") (part "R_0805"))
    )
    (comp (ref "R77")
      (value "100K")
      (footprint "eagle-import:R0805")
      (fields (field (name "PARTNO") "ERJ-6ENF1003V"))
      (libsource (lib "eagle-import") (part "R_0805"))
    )
    (comp (ref "R78")
      (value "100K")
      (footprint "eagle-import:R0805")
      (fields (field (name "PARTNO") "ERJ-6ENF1003V"))
      (libsource (lib "eagle-import") (part "R_0805"))
    )
    (comp (ref "R79")
      (value "10K")
      (footprint "eagle-import:R0805")
      (fields (field (name "PARTNO") "ERJ-6ENF1002V"))
      (libsource (lib "eagle-import") (part "R_0805"))
    )
    (comp (ref "R82")
      (value "1.00K")
      (footprint "eagle-import:R0805")
      (fields (field (name "PARTNO") "ERJ-6ENF1001V"))
      (libsource (lib "eagle-import") (part "R_0805"))
    )
    (comp (ref "R83")
      (value "1.00K")
      (footprint "eagle-import:R0805")
      (fields (field (name "PARTNO") "ERJ-6ENF1001V"))
      (libsource (lib "eagle-import") (part "R_0805"))
    )
    (comp (ref "TP3")
      (value "TPTP10SQ")
      (footprint "eagle-import:TP10SQ")
      (libsource (lib "eagle-import") (part "TPTP10SQ"))
    )
    (comp (ref "TP4")
      (value "TPTP10SQ")
      (footprint "eagle-import:TP10SQ")
      (libsource (lib "eagle-import") (part "TPTP10SQ"))
    )
    (comp (ref "TP5")
      (value "TPTP10SQ")
      (footprint "eagle-import:TP10SQ")
      (libsource (lib "eagle-import") (part "TPTP10SQ"))
    )
    (comp (ref "TP6")
      (value "TPTP10SQ")
      (footprint "eagle-import:TP10SQ")
      (libsource (lib "eagle-import") (part "TPTP10SQ"))
    )
    (comp (ref "TP7")
      (value "TPTP10SQ")
      (footprint "eagle-import:TP10SQ")
      (libsource (lib "eagle-import") (part "TPTP10SQ"))
    )
    (comp (ref "TP8")
      (value "TPS-SMD-10SN")
      (footprint "eagle-import:SMD-10SN")
      (fields (field (name "BOM") "EXCLUDE"))
      (libsource (lib "eagle-import") (part "TPS-SMD-10SN"))
    )
    (comp (ref "TP10")
      (value "TPS-SMD-10SN")
      (footprint "eagle-import:SMD-10SN")
      (fields (field (name "BOM") "EXCLUDE") (field (name "LABEL") "GND"))
      (libsource (lib "eagle-import") (part "TPS-SMD-10SN"))
    )
    (comp (ref "U5")
      (value "LM324D")
      (footprint "eagle-import:SO14")
      (fields (field (name "PARTNO") "LM324D"))
      (libsource (lib "eagle-import") (part "LM324D"))
    )
    (comp (ref "U6")
      (value "MT8870DS")
      (footprint "eagle-import:SO18W")
      (fields (field (name "PARTNO") "MT8870DS"))
      (libsource (lib "eagle-import") (part "CM8870CS"))
    )
    (comp (ref "U7")
      (value "MAX323CSA+")
      (footprint "eagle-import:SO08")
      (fields (field (name "PARTNO") "MAX323CSA+"))
      (libsource (lib "eagle-import") (part "MAX323CSA"))
    )
    (comp (ref "U8")
      (value "MX828DW")
      (footprint "eagle-import:SSOP24")
      (fields (field (name "PARTNO") "MX828DW"))
      (libsource (lib "eagle-import") (part "MX828DS"))
    )
    (comp (ref "U9")
      (value "ISD4002-240SY")
      (footprint "eagle-import:SO28W")
      (libsource (lib "eagle-import") (part "ISD4002S"))
    )
    (comp (ref "U10")
      (value "TLC084CD")
      (footprint "eagle-import:SO14")
      (fields (field (name "PARTNO") "TLC084CD"))
      (libsource (lib "eagle-import") (part "TL084D"))
    )
    (comp (ref "Y2")
      (value "3.579 MHZ")
      (footprint "eagle-import:TC310H")
      (fields (field (name "PARTNO") "ECS-35-18-10X"))
      (libsource (lib "eagle-import") (part "CRYTALTC310H"))
    )
    (comp (ref "Y3")
      (value "4.032MHZ")
      (footprint "eagle-import:SM49")
      (fields (field (name "PARTNO") "ECS-40.3-20-5PX-TR"))
      (libsource (lib "eagle-import") (part "CRYTALSM49"))
    )
  )
  (nets
    (net (code "1") (name "+2V5") (class "Default")
      (node (ref "R16") (pin "2") (pinfunction "2_2") (pintype "passive"))
      (node (ref "R46") (pin "2") (pinfunction "2_2") (pintype "passive"))
      (node (ref "R62") (pin "2") (pinfunction "2_2") (pintype "passive"))
      (node (ref "U10") (pin "1") (pinfunction "OUT_1") (pintype "output"))
      (node (ref "U10") (pin "2") (pinfunction "-IN_2") (pintype "input"))
    )
    (net (code "2") (name "+3V3") (class "Default")
      (node (ref "C21") (pin "+") (pinfunction "+_+") (pintype "passive"))
      (node (ref "C68") (pin "+") (pinfunction "+_+") (pintype "passive"))
      (node (ref "C69") (pin "1") (pinfunction "1_1") (pintype "passive"))
      (node (ref "C70") (pin "+") (pinfunction "+_+") (pintype "passive"))
      (node (ref "C71") (pin "1") (pinfunction "1_1") (pintype "passive"))
      (node (ref "TP2") (pin "TP") (pinfunction "TP_TP") (pintype "input"))
      (node (ref "U4") (pin "1") (pinfunction "OUT_1") (pintype "passive"))
      (node (ref "U9") (pin "18") (pinfunction "VCCA_18") (pintype "power_in"))
      (node (ref "U9") (pin "27") (pinfunction "VCCD_27") (pintype "power_in"))
    )
    (net (code "3") (name "+5V") (class "Default")
      (node (ref "C11") (pin "1") (pinfunction "1_1") (pintype "passive"))
      (node (ref "C22") (pin "1") (pinfunction "1_1") (pintype "passive"))
      (node (ref "C28") (pin "+") (pinfunction "+_+") (pintype "passive"))
      (node (ref "C30") (pin "2") (pinfunction "2_2") (pintype "passive"))
      (node (ref "C72") (pin "1") (pinfunction "1_1") (pintype "passive"))
      (node (ref "C73") (pin "1") (pinfunction "1_1") (pintype "passive"))
      (node (ref "C74") (pin "+") (pinfunction "+_+") (pintype "passive"))
      (node (ref "C9") (pin "1") (pinfunction "1_1") (pintype "passive"))
      (node (ref "D5") (pin "A") (pinfunction "A_A") (pintype "passive"))
      (node (ref "D9") (pin "C") (pinfunction "C_C") (pintype "passive"))
      (node (ref "J1") (pin "2") (pinfunction "VDD_2") (pintype "power_in"))
      (node (ref "J2") (pin "8") (pinfunction "8_8") (pintype "passive"))
      (node (ref "JP1") (pin "4") (pinfunction "4_4") (pintype "passive"))
      (node (ref "JP1") (pin "7") (pinfunction "7_7") (pintype "passive"))
      (node (ref "JP2") (pin "2") (pinfunction "2_2") (pintype "passive"))
      (node (ref "L3") (pin "2") (pinfunction "2_2") (pintype "passive"))
      (node (ref "R10") (pin "2") (pinfunction "2_2") (pintype "passive"))
      (node (ref "R11") (pin "2") (pinfunction "2_2") (pintype "passive"))
      (node (ref "R18") (pin "2") (pinfunction "2_2") (pintype "passive"))
      (node (ref "R2") (pin "1") (pinfunction "1_1") (pintype "passive"))
      (node (ref "R20") (pin "2") (pinfunction "2_2") (pintype "passive"))
      (node (ref "R50") (pin "1") (pinfunction "1_1") (pintype "passive"))
      (node (ref "R6") (pin "1") (pinfunction "1_1") (pintype "passive"))
      (node (ref "R69") (pin "2") (pinfunction "2_2") (pintype "passive"))
      (node (ref "R7") (pin "1") (pinfunction "1_1") (pintype "passive"))
      (node (ref "R70") (pin "2") (pinfunction "2_2") (pintype "passive"))
      (node (ref "R74") (pin "2") (pinfunction "2_2") (pintype "passive"))
      (node (ref "R79") (pin "2") (pinfunction "2_2") (pintype "passive"))
      (node (ref "RN1") (pin "5") (pinfunction "5_5") (pintype "passive"))
      (node (ref "RN1") (pin "6") (pinfunction "6_6") (pintype "passive"))
      (node (ref "RN1") (pin "7") (pinfunction "7_7") (pintype "passive"))
      (node (ref "RN1") (pin "8") (pinfunction "8_8") (pintype "passive"))
      (node (ref "TP1") (pin "TP") (pinfunction "TP_TP") (pintype "input"))
      (node (ref "U1") (pin "8") (pinfunction "VCC_8") (pintype "power_in"))
      (node (ref "U11") (pin "3") (pinfunction "OUT_3") (pintype "passive"))
      (node (ref "U3") (pin "22") (pinfunction "~{FORCEOFF}_22") (pintype "input"))
      (node (ref "U3") (pin "26") (pinfunction "VCC_26") (pintype "power_in"))
      (node (ref "U6") (pin "18") (pinfunction "VDD_18") (pintype "power_in"))
      (node (ref "U8") (pin "24") (pinfunction "VDD_24") (pintype "power_in"))
    )
    (net (code "4") (name "+12V") (class "Default")
      (node (ref "C25") (pin "1") (pinfunction "1_1") (pintype "passive"))
      (node (ref "C26") (pin "+") (pinfunction "+_+") (pintype "passive"))
      (node (ref "C27") (pin "+") (pinfunction "+_+") (pintype "passive"))
      (node (ref "C75") (pin "1") (pinfunction "1_1") (pintype "passive"))
      (node (ref "C76") (pin "1") (pinfunction "1_1") (pintype "passive"))
      (node (ref "C77") (pin "1") (pinfunction "1_1") (pintype "passive"))
      (node (ref "D5") (pin "C") (pinfunction "C_C") (pintype "passive"))
      (node (ref "D6") (pin "C") (pinfunction "C_C") (pintype "passive"))
      (node (ref "D8") (pin "C") (pinfunction "C_C") (pintype "passive"))
      (node (ref "J2") (pin "9") (pinfunction "9_9") (pintype "passive"))
      (node (ref "R21") (pin "2") (pinfunction "2_2") (pintype "passive"))
      (node (ref "R73") (pin "2") (pinfunction "2_2") (pintype "passive"))
      (node (ref "TP9") (pin "TP") (pinfunction "TP_TP") (pintype "input"))
      (node (ref "U10") (pin "4") (pinfunction "V+_4") (pintype "power_in"))
      (node (ref "U11") (pin "1") (pinfunction "IN_1") (pintype "input"))
      (node (ref "U4") (pin "3") (pinfunction "IN_3") (pintype "input"))
      (node (ref "U5") (pin "4") (pinfunction "V+_4") (pintype "power_in"))
      (node (ref "U7") (pin "8") (pinfunction "V+_8") (pintype "power_in"))
    )
    (net (code "6") (name "AGND") (class "Default")
      (node (ref "C19") (pin "2") (pinfunction "2_2") (pintype "passive"))
      (node (ref "C20") (pin "2") (pinfunction "2_2") (pintype "passive"))
      (node (ref "C38") (pin "1") (pinfunction "1_1") (pintype "passive"))
      (node (ref "C4") (pin "1") (pinfunction "1_1") (pintype "passive"))
      (node (ref "C55") (pin "-") (pinfunction "-_-") (pintype "passive"))
      (node (ref "C56") (pin "-") (pinfunction "-_-") (pintype "passive"))
      (node (ref "C57") (pin "2") (pinfunction "2_2") (pintype "passive"))
      (node (ref "C60") (pin "2") (pinfunction "2_2") (pintype "passive"))
      (node (ref "C62") (pin "2") (pinfunction "2_2") (pintype "passive"))
      (node (ref "C63") (pin "1") (pinfunction "1_1") (pintype "passive"))
      (node (ref "C65") (pin "2") (pinfunction "2_2") (pintype "passive"))
      (node (ref "C66") (pin "2") (pinfunction "2_2") (pintype "passive"))
      (node (ref "C67") (pin "-") (pinfunction "-_-") (pintype "passive"))
      (node (ref "C68") (pin "-") (pinfunction "-_-") (pintype "passive"))
      (node (ref "C69") (pin "2") (pinfunction "2_2") (pintype "passive"))
      (node (ref "C75") (pin "2") (pinfunction "2_2") (pintype "passive"))
      (node (ref "C76") (pin "2") (pinfunction "2_2") (pintype "passive"))
      (node (ref "C77") (pin "2") (pinfunction "2_2") (pintype "passive"))
      (node (ref "C78") (pin "-") (pinfunction "-_-") (pintype "passive"))
      (node (ref "C79") (pin "-") (pinfunction "-_-") (pintype "passive"))
      (node (ref "C8") (pin "2") (pinfunction "2_2") (pintype "passive"))
      (node (ref "D10") (pin "A") (pinfunction "A_A") (pintype "passive"))
      (node (ref "D7") (pin "A") (pinfunction "A_A") (pintype "passive"))
      (node (ref "J2") (pin "7") (pinfunction "7_7") (pintype "passive"))
      (node (ref "R22") (pin "1") (pinfunction "1_1") (pintype "passive"))
      (node (ref "R23") (pin "1") (pinfunction "1_1") (pintype "passive"))
      (node (ref "R26") (pin "1") (pinfunction "1_1") (pintype "passive"))
      (node (ref "R27") (pin "1") (pinfunction "1_1") (pintype "passive"))
      (node (ref "R33") (pin "1") (pinfunction "1_1") (pintype "passive"))
      (node (ref "R37") (pin "2") (pinfunction "2_2") (pintype "passive"))
      (node (ref "R38") (pin "2") (pinfunction "2_2") (pintype "passive"))
      (node (ref "R39") (pin "2") (pinfunction "2_2") (pintype "passive"))
      (node (ref "R40") (pin "2") (pinfunction "2_2") (pintype "passive"))
      (node (ref "R49") (pin "1") (pinfunction "1_1") (pintype "passive"))
      (node (ref "R61") (pin "1") (pinfunction "1_1") (pintype "passive"))
      (node (ref "R63") (pin "1") (pinfunction "1_1") (pintype "passive"))
      (node (ref "R66") (pin "1") (pinfunction "1_1") (pintype "passive"))
      (node (ref "R67") (pin "2") (pinfunction "2_2") (pintype "passive"))
      (node (ref "R71") (pin "1") (pinfunction "1_1") (pintype "passive"))
      (node (ref "R75") (pin "1") (pinfunction "1_1") (pintype "passive"))
      (node (ref "R77") (pin "1") (pinfunction "1_1") (pintype "passive"))
      (node (ref "R78") (pin "1") (pinfunction "1_1") (pintype "passive"))
      (node (ref "R80") (pin "2") (pinfunction "2_2") (pintype "passive"))
      (node (ref "TP10") (pin "TP") (pinfunction "TP_TP") (pintype "passive"))
      (node (ref "U10") (pin "11") (pinfunction "V-_11") (pintype "power_in"))
      (node (ref "U12") (pin "2") (pinfunction "GND_2") (pintype "input"))
      (node (ref "U5") (pin "11") (pinfunction "V-_11") (pintype "power_in"))
      (node (ref "U7") (pin "4") (pinfunction "V-_4") (pintype "power_in"))
      (node (ref "U9") (pin "11") (pinfunction "VSSA_11") (pintype "power_in"))
      (node (ref "U9") (pin "12") (pinfunction "VSSA_12") (pintype "power_in"))
      (node (ref "U9") (pin "23") (pinfunction "VSSA_23") (pintype "power_in"))
      (node (ref "X3") (pin "5") (pinfunction "5_5") (pintype "passive"))
      (node (ref "X4") (pin "5") (pinfunction "5_5") (pintype "passive"))
    )
    (net (code "7") (name "AUX_AUDIO") (class "Default")
      (node (ref "C45") (pin "2") (pinfunction "2_2") (pintype "passive"))
      (node (ref "J2") (pin "3") (pinfunction "3_3") (pintype "passive"))
      (node (ref "R49") (pin "2") (pinfunction "2_2") (pintype "passive"))
      (node (ref "X3") (pin "8") (pinfunction "8_8") (pintype "passive"))
      (node (ref "X4") (pin "8") (pinfunction "8_8") (pintype "passive"))
    )
    (net (code "8") (name "AUX_AUDIO_OUT") (class "Default")
      (node (ref "TP4") (pin "TP") (pinfunction "TP_TP") (pintype "input"))
      (node (ref "U7") (pin "1") (pinfunction "NO_1") (pintype "passive"))
      (node (ref "U8") (pin "22") (pinfunction "MOD1_22") (pintype "output"))
    )
    (net (code "9") (name "AVR_5V") (class "Default")
      (node (ref "C1") (pin "1") (pinfunction "1_1") (pintype "passive"))
      (node (ref "C2") (pin "1") (pinfunction "1_1") (pintype "passive"))
      (node (ref "D1") (pin "C") (pinfunction "C_C") (pintype "passive"))
      (node (ref "L2") (pin "2") (pinfunction "2_2") (pintype "passive"))
      (node (ref "R5") (pin "2") (pinfunction "2_2") (pintype "passive"))
      (node (ref "U2") (pin "21") (pinfunction "VCC_21") (pintype "power_in"))
      (node (ref "U2") (pin "52") (pinfunction "VCC1_52") (pintype "power_in"))
    )
    (net (code "10") (name "AVR_REF") (class "Default")
      (node (ref "C4") (pin "2") (pinfunction "2_2") (pintype "passive"))
      (node (ref "U12") (pin "1") (pinfunction "OUT_1") (pintype "passive"))
      (node (ref "U2") (pin "64") (pinfunction "AVCC_64") (pintype "bidirectional"))
    )
    (net (code "11") (name "BEEP_PWM") (class "Default")
      (node (ref "R68") (pin "1") (pinfunction "1_1") (pintype "passive"))
      (node (ref "TP7") (pin "TP") (pinfunction "TP_TP") (pintype "input"))
      (node (ref "U2") (pin "15") (pinfunction "(OC1A/PCINT5)PB5_15") (pintype "bidirectional"))
    )
    (net (code "12") (name "B_CTS") (class "Default")
      (node (ref "U3") (pin "6") (pinfunction "R3IN_6") (pintype "input"))
      (node (ref "X2") (pin "8") (pinfunction "8_8") (pintype "passive"))
    )
    (net (code "13") (name "B_DCD") (class "Default")
      (node (ref "U3") (pin "8") (pinfunction "R5IN_8") (pintype "input"))
      (node (ref "X2") (pin "1") (pinfunction "1_1") (pintype "passive"))
    )
    (net (code "14") (name "B_DSR") (class "Default")
      (node (ref "U3") (pin "7") (pinfunction "R4IN_7") (pintype "input"))
      (node (ref "X2") (pin "6") (pinfunction "6_6") (pintype "passive"))
    )
    (net (code "15") (name "B_DTR") (class "Default")
      (node (ref "U3") (pin "10") (pinfunction "T2OUT_10") (pintype "output"))
      (node (ref "X2") (pin "4") (pinfunction "4_4") (pintype "passive"))
    )
    (net (code "16") (name "B_RI") (class "Default")
      (node (ref "U3") (pin "4") (pinfunction "R1IN_4") (pintype "input"))
      (node (ref "X2") (pin "9") (pinfunction "9_9") (pintype "passive"))
    )
    (net (code "17") (name "B_RTS") (class "Default")
      (node (ref "U3") (pin "11") (pinfunction "T3OUT_11") (pintype "output"))
      (node (ref "X2") (pin "7") (pinfunction "7_7") (pintype "passive"))
    )
    (net (code "18") (name "B_RXD") (class "Default")
      (node (ref "U3") (pin "5") (pinfunction "R2IN_5") (pintype "input"))
      (node (ref "X2") (pin "2") (pinfunction "2_2") (pintype "passive"))
    )
    (net (code "19") (name "B_TXD") (class "Default")
      (node (ref "U3") (pin "9") (pinfunction "T1OUT_9") (pintype "output"))
      (node (ref "X2") (pin "3") (pinfunction "3_3") (pintype "passive"))
    )
    (net (code "20") (name "CGND") (class "Default")
      (node (ref "C23") (pin "2") (pinfunction "2_2") (pintype "passive"))
      (node (ref "C24") (pin "2") (pinfunction "2_2") (pintype "passive"))
      (node (ref "C25") (pin "2") (pinfunction "2_2") (pintype "passive"))
      (node (ref "C26") (pin "-") (pinfunction "-_-") (pintype "passive"))
      (node (ref "C27") (pin "-") (pinfunction "-_-") (pintype "passive"))
      (node (ref "C28") (pin "-") (pinfunction "-_-") (pintype "passive"))
      (node (ref "C80") (pin "2") (pinfunction "2_2") (pintype "passive"))
      (node (ref "D8") (pin "A") (pinfunction "A_A") (pintype "passive"))
      (node (ref "D9") (pin "A") (pinfunction "A_A") (pintype "passive"))
      (node (ref "L1") (pin "4") (pinfunction "4_4") (pintype "passive"))
      (node (ref "Q3") (pin "3") (pinfunction "S_3") (pintype "passive"))
      (node (ref "Q4") (pin "3") (pinfunction "S_3") (pintype "passive"))
      (node (ref "R13") (pin "2") (pinfunction "2_2") (pintype "passive"))
      (node (ref "R80") (pin "1") (pinfunction "1_1") (pintype "passive"))
      (node (ref "R81") (pin "1") (pinfunction "1_1") (pintype "passive"))
      (node (ref "U11") (pin "2") (pinfunction "GND_2") (pintype "input"))
      (node (ref "X3") (pin "4") (pinfunction "4_4") (pintype "passive"))
      (node (ref "X4") (pin "4") (pinfunction "4_4") (pintype "passive"))
    )
    (net (code "21") (name "COM_CTS") (class "Default")
      (node (ref "U2") (pin "14") (pinfunction "(OC2A/PCINT4)PB4_14") (pintype "bidirectional"))
      (node (ref "U3") (pin "17") (pinfunction "R3OUT_17") (pintype "output"))
    )
    (net (code "22") (name "COM_DCD") (class "Default")
      (node (ref "U2") (pin "8") (pinfunction "(T3/INT6)PE6_8") (pintype "bidirectional"))
      (node (ref "U3") (pin "15") (pinfunction "R5OUT_15") (pintype "output"))
    )
    (net (code "23") (name "COM_DSR") (class "Default")
      (node (ref "U2") (pin "17") (pinfunction "(OC0A/OC1C/PCINT7)PB7_17") (pintype "bidirectional"))
      (node (ref "U3") (pin "16") (pinfunction "R4OUT_16") (pintype "output"))
    )
    (net (code "24") (name "COM_DTR") (class "Default")
      (node (ref "U2") (pin "35") (pinfunction "(A8)PC0_35") (pintype "output"))
      (node (ref "U3") (pin "12") (pinfunction "T3IN_12") (pintype "input"))
      (node (ref "U3") (pin "13") (pinfunction "T2IN_13") (pintype "input"))
    )
    (net (code "25") (name "COM_RXD") (class "Default")
      (node (ref "R3") (pin "2") (pinfunction "2_2") (pintype "passive"))
      (node (ref "U2") (pin "2") (pinfunction "(RXD0/PCINT8/PDI)PE0_2") (pintype "bidirectional"))
      (node (ref "U3") (pin "18") (pinfunction "R2OUT_18") (pintype "output"))
    )
    (net (code "26") (name "COM_TXD") (class "Default")
      (node (ref "R1") (pin "2") (pinfunction "2_2") (pintype "passive"))
      (node (ref "U2") (pin "3") (pinfunction "(TXD0/PDO)PE1_3") (pintype "bidirectional"))
      (node (ref "U3") (pin "14") (pinfunction "T1IN_14") (pintype "input"))
    )
    (net (code "27") (name "COS") (class "Default")
      (node (ref "R13") (pin "1") (pinfunction "1_1") (pintype "passive"))
      (node (ref "R19") (pin "2") (pinfunction "2_2") (pintype "passive"))
      (node (ref "X3") (pin "3") (pinfunction "3_3") (pintype "passive"))
      (node (ref "X4") (pin "3") (pinfunction "3_3") (pintype "passive"))
    )
    (net (code "28") (name "CS_DTMF") (class "Default")
      (node (ref "U2") (pin "38") (pinfunction "(A11)PC3_38") (pintype "output"))
      (node (ref "U6") (pin "10") (pinfunction "TOE_10") (pintype "input"))
    )
    (net (code "29") (name "DISC_AUDIO") (class "Default")
      (node (ref "R26") (pin "3") (pinfunction "3_3") (pintype "passive"))
      (node (ref "R27") (pin "3") (pinfunction "3_3") (pintype "passive"))
      (node (ref "X3") (pin "6") (pinfunction "6_6") (pintype "passive"))
      (node (ref "X4") (pin "6") (pinfunction "6_6") (pintype "passive"))
    )
    (net (code "30") (name "DTMF_Q1") (class "Default")
      (node (ref "U2") (pin "29") (pinfunction "(ICP1)PD4_29") (pintype "bidirectional"))
      (node (ref "U6") (pin "11") (pinfunction "Q1_11") (pintype "output"))
    )
    (net (code "31") (name "DTMF_Q2") (class "Default")
      (node (ref "U2") (pin "30") (pinfunction "(XCK1)PD5_30") (pintype "bidirectional"))
      (node (ref "U6") (pin "12") (pinfunction "Q2_12") (pintype "output"))
    )
    (net (code "32") (name "DTMF_Q3") (class "Default")
      (node (ref "U2") (pin "31") (pinfunction "(T1)PD6_31") (pintype "bidirectional"))
      (node (ref "U6") (pin "13") (pinfunction "Q3_13") (pintype "output"))
    )
    (net (code "33") (name "DTMF_Q4") (class "Default")
      (node (ref "U2") (pin "32") (pinfunction "(T2)PD7_32") (pintype "bidirectional"))
      (node (ref "U6") (pin "14") (pinfunction "Q4_14") (pintype "output"))
    )
    (net (code "34") (name "EXP_IO0") (class "Default")
      (node (ref "J2") (pin "15") (pinfunction "15_15") (pintype "passive"))
      (node (ref "U2") (pin "4") (pinfunction "(XCK0/AIN0)PE2_4") (pintype "bidirectional"))
    )
    (net (code "35") (name "EXP_IO1") (class "Default")
      (node (ref "J2") (pin "19") (pinfunction "19_19") (pintype "passive"))
      (node (ref "U2") (pin "5") (pinfunction "(OC3A/AIN1)PE3_5") (pintype "bidirectional"))
    )
    (net (code "36") (name "EXP_IO2") (class "Default")
      (node (ref "J2") (pin "17") (pinfunction "17_17") (pintype "passive"))
      (node (ref "U2") (pin "37") (pinfunction "(A10)PC2_37") (pintype "output"))
    )
    (net (code "37") (name "EXT_COS") (class "Default")
      (node (ref "Q5") (pin "3") (pinfunction "C_3") (pintype "passive"))
      (node (ref "R18") (pin "1") (pinfunction "1_1") (pintype "passive"))
      (node (ref "U2") (pin "34") (pinfunction "PG1(RD#)_34") (pintype "bidirectional"))
    )
    (net (code "38") (name "FAN") (class "Default")
      (node (ref "Q4") (pin "2") (pinfunction "D_2") (pintype "passive"))
      (node (ref "X3") (pin "2") (pinfunction "2_2") (pintype "passive"))
      (node (ref "X4") (pin "2") (pinfunction "2_2") (pintype "passive"))
    )
    (net (code "39") (name "FAN_DRIVE") (class "Default")
      (node (ref "R17") (pin "1") (pinfunction "1_1") (pintype "passive"))
      (node (ref "U2") (pin "39") (pinfunction "(A12)PC4_39") (pintype "output"))
    )
    (net (code "40") (name "GND") (class "Default")
      (node (ref "B1") (pin "-") (pinfunction "-_-") (pintype "passive"))
      (node (ref "C1") (pin "2") (pinfunction "2_2") (pintype "passive"))
      (node (ref "C12") (pin "1") (pinfunction "1_1") (pintype "passive"))
      (node (ref "C2") (pin "2") (pinfunction "2_2") (pintype "passive"))
      (node (ref "C21") (pin "-") (pinfunction "-_-") (pintype "passive"))
      (node (ref "C22") (pin "2") (pinfunction "2_2") (pintype "passive"))
      (node (ref "C3") (pin "-") (pinfunction "-_-") (pintype "passive"))
      (node (ref "C5") (pin "2") (pinfunction "2_2") (pintype "passive"))
      (node (ref "C53") (pin "2") (pinfunction "2_2") (pintype "passive"))
      (node (ref "C54") (pin "2") (pinfunction "2_2") (pintype "passive"))
      (node (ref "C6") (pin "2") (pinfunction "2_2") (pintype "passive"))
      (node (ref "C7") (pin "2") (pinfunction "2_2") (pintype "passive"))
      (node (ref "C70") (pin "-") (pinfunction "-_-") (pintype "passive"))
      (node (ref "C71") (pin "2") (pinfunction "2_2") (pintype "passive"))
      (node (ref "C72") (pin "2") (pinfunction "2_2") (pintype "passive"))
      (node (ref "C73") (pin "2") (pinfunction "2_2") (pintype "passive"))
      (node (ref "C74") (pin "-") (pinfunction "-_-") (pintype "passive"))
      (node (ref "C9") (pin "2") (pinfunction "2_2") (pintype "passive"))
      (node (ref "D2") (pin "A") (pinfunction "A_A") (pintype "passive"))
      (node (ref "J1") (pin "1") (pinfunction "VSS_1") (pintype "power_in"))
      (node (ref "J2") (pin "6") (pinfunction "6_6") (pintype "passive"))
      (node (ref "JP1") (pin "10") (pinfunction "10_10") (pintype "passive"))
      (node (ref "JP1") (pin "2") (pinfunction "2_2") (pintype "passive"))
      (node (ref "JP2") (pin "6") (pinfunction "6_6") (pintype "passive"))
      (node (ref "JP5") (pin "1") (pinfunction "1_1") (pintype "passive"))
      (node (ref "JP5") (pin "3") (pinfunction "3_3") (pintype "passive"))
      (node (ref "Q1") (pin "2") (pinfunction "E_2") (pintype "passive"))
      (node (ref "Q2") (pin "3") (pinfunction "S_3") (pintype "passive"))
      (node (ref "Q5") (pin "2") (pinfunction "E_2") (pintype "passive"))
      (node (ref "R2") (pin "3") (pinfunction "3_3") (pintype "passive"))
      (node (ref "R81") (pin "2") (pinfunction "2_2") (pintype "passive"))
      (node (ref "U1") (pin "4") (pinfunction "GND_4") (pintype "power_in"))
      (node (ref "U2") (pin "22") (pinfunction "GND_22") (pintype "power_in"))
      (node (ref "U2") (pin "53") (pinfunction "GND1_53") (pintype "power_in"))
      (node (ref "U2") (pin "63") (pinfunction "GND2_63") (pintype "power_in"))
      (node (ref "U3") (pin "23") (pinfunction "FORCEON_23") (pintype "input"))
      (node (ref "U3") (pin "25") (pinfunction "GND_25") (pintype "power_in"))
      (node (ref "U4") (pin "2") (pinfunction "GND_2") (pintype "input"))
      (node (ref "U4") (pin "4") (pinfunction "GND_4") (pintype "input"))
      (node (ref "U6") (pin "5") (pinfunction "INH_5") (pintype "input"))
      (node (ref "U6") (pin "6") (pinfunction "PD_6") (pintype "input"))
      (node (ref "U6") (pin "9") (pinfunction "VSS_9") (pintype "power_in"))
      (node (ref "U8") (pin "12") (pinfunction "VSS_12") (pintype "power_in"))
      (node (ref "U9") (pin "26") (pinfunction "XCLK_26") (pintype "input"))
      (node (ref "U9") (pin "4") (pinfunction "VSSD_4") (pintype "power_in"))
      (node (ref "X2") (pin "5") (pinfunction "5_5") (pintype "passive"))
      (node (ref "X2") (pin "G1") (pinfunction "G1_G1") (pintype "passive"))
      (node (ref "X2") (pin "G2") (pinfunction "G2_G2") (pintype "passive"))
    )
    (net (code "41") (name "I2C_SCL") (class "Default")
      (node (ref "J2") (pin "13") (pinfunction "13_13") (pintype "passive"))
      (node (ref "R10") (pin "1") (pinfunction "1_1") (pintype "passive"))
      (node (ref "U1") (pin "6") (pinfunction "SCL_6") (pintype "bidirectional"))
      (node (ref "U2") (pin "25") (pinfunction "(SCL/INT0)PD0_25") (pintype "bidirectional"))
    )
    (net (code "42") (name "I2C_SDA") (class "Default")
      (node (ref "J2") (pin "11") (pinfunction "11_11") (pintype "passive"))
      (node (ref "R11") (pin "1") (pinfunction "1_1") (pintype "passive"))
      (node (ref "U1") (pin "5") (pinfunction "SDA_5") (pintype "bidirectional"))
      (node (ref "U2") (pin "26") (pinfunction "(SDA/INT1)PD1_26") (pintype "bidirectional"))
    )
    (net (code "43") (name "INT_DTMF") (class "Default")
      (node (ref "U2") (pin "6") (pinfunction "(OC3B/INT4)PE4_6") (pintype "bidirectional"))
      (node (ref "U6") (pin "15") (pinfunction "STD_15") (pintype "input"))
    )
    (net (code "44") (name "INT_EXP") (class "Default")
      (node (ref "J2") (pin "18") (pinfunction "18_18") (pintype "passive"))
      (node (ref "R79") (pin "1") (pinfunction "1_1") (pintype "passive"))
      (node (ref "U2") (pin "27") (pinfunction "(RXD1/INT2)PD2_27") (pintype "bidirectional"))
    )
    (net (code "45") (name "INT_ISD") (class "Default")
      (node (ref "R69") (pin "1") (pinfunction "1_1") (pintype "passive"))
      (node (ref "U2") (pin "7") (pinfunction "(OC3C/INT5)PE5_7") (pintype "bidirectional"))
      (node (ref "U9") (pin "25") (pinfunction "~{INT}_25") (pintype "output"))
    )
    (net (code "46") (name "INT_MX828") (class "Default")
      (node (ref "R50") (pin "2") (pinfunction "2_2") (pintype "passive"))
      (node (ref "U2") (pin "28") (pinfunction "(TXD1/INT3)PD3_28") (pintype "bidirectional"))
      (node (ref "U8") (pin "7") (pinfunction "~{IRQ}_7") (pintype "output"))
    )
    (net (code "47") (name "INT_RAC") (class "Default")
      (node (ref "R70") (pin "1") (pinfunction "1_1") (pintype "passive"))
      (node (ref "U2") (pin "9") (pinfunction "(ICP3/CLKO/INT7)PE7_9") (pintype "bidirectional"))
      (node (ref "U9") (pin "24") (pinfunction "RAC_24") (pintype "output"))
    )
    (net (code "48") (name "LCD_BKLITE") (class "Default")
      (node (ref "R9") (pin "1") (pinfunction "1_1") (pintype "passive"))
      (node (ref "U2") (pin "1") (pinfunction "PG5(OC0B)_1") (pintype "bidirectional"))
    )
    (net (code "49") (name "LCD_E") (class "Default")
      (node (ref "J1") (pin "6") (pinfunction "E_6") (pintype "input"))
      (node (ref "U2") (pin "41") (pinfunction "(A14)PC6_41") (pintype "output"))
    )
    (net (code "50") (name "LCD_RS") (class "Default")
      (node (ref "J1") (pin "4") (pinfunction "RS_4") (pintype "input"))
      (node (ref "U2") (pin "40") (pinfunction "(A13)PC5_40") (pintype "output"))
    )
    (net (code "51") (name "LCD_RW") (class "Default")
      (node (ref "J1") (pin "5") (pinfunction "R/W_5") (pintype "input"))
      (node (ref "U2") (pin "42") (pinfunction "(A15)PC7_42") (pintype "output"))
    )
    (net (code "52") (name "LED_PWR") (class "Default")
      (node (ref "R8") (pin "1") (pinfunction "1_1") (pintype "passive"))
      (node (ref "U2") (pin "43") (pinfunction "PG2(ALE)_43") (pintype "bidirectional"))
    )
    (net (code "53") (name "MIX_BUSS") (class "Default")
      (node (ref "C51") (pin "1") (pinfunction "1_1") (pintype "passive"))
      (node (ref "R51") (pin "2") (pinfunction "2_2") (pintype "passive"))
      (node (ref "R59") (pin "2") (pinfunction "2_2") (pintype "passive"))
      (node (ref "R64") (pin "2") (pinfunction "2_2") (pintype "passive"))
      (node (ref "R72") (pin "1") (pinfunction "1_1") (pintype "passive"))
      (node (ref "R76") (pin "2") (pinfunction "2_2") (pintype "passive"))
    )
    (net (code "54") (name "MIX_INSERT") (class "Default")
      (node (ref "C47") (pin "1") (pinfunction "1_1") (pintype "passive"))
      (node (ref "J2") (pin "4") (pinfunction "4_4") (pintype "passive"))
      (node (ref "R16") (pin "1") (pinfunction "1_1") (pintype "passive"))
    )
    (net (code "55") (name "MUTE_AUX") (class "Default")
      (node (ref "U2") (pin "18") (pinfunction "PG3(TOSC2)_18") (pintype "bidirectional"))
      (node (ref "U7") (pin "7") (pinfunction "IN_7") (pintype "input"))
    )
    (net (code "56") (name "MUTE_RX") (class "Default")
      (node (ref "U2") (pin "19") (pinfunction "PG4(TOSC1)_19") (pintype "bidirectional"))
      (node (ref "U7") (pin "3") (pinfunction "IN_3") (pintype "input"))
    )
    (net (code "57") (name "Net-(C24-Pad1)") (class "Default")
      (node (ref "C24") (pin "1") (pinfunction "1_1") (pintype "passive"))
      (node (ref "D6") (pin "A") (pinfunction "A_A") (pintype "passive"))
      (node (ref "L4") (pin "2") (pinfunction "2_2") (pintype "passive"))
    )
    (net (code "58") (name "Net-(C31-Pad1)") (class "Default")
      (node (ref "C31") (pin "1") (pinfunction "1_1") (pintype "passive"))
      (node (ref "R27") (pin "2") (pinfunction "2_2") (pintype "passive"))
    )
    (net (code "59") (name "Net-(C31-Pad2)") (class "Default")
      (node (ref "C31") (pin "2") (pinfunction "2_2") (pintype "passive"))
      (node (ref "R28") (pin "1") (pinfunction "1_1") (pintype "passive"))
    )
    (net (code "60") (name "Net-(C32-Pad2)") (class "Default")
      (node (ref "C32") (pin "2") (pinfunction "2_2") (pintype "passive"))
      (node (ref "C33") (pin "1") (pinfunction "1_1") (pintype "passive"))
      (node (ref "R33") (pin "2") (pinfunction "2_2") (pintype "passive"))
    )
    (net (code "61") (name "Net-(C33-Pad2)") (class "Default")
      (node (ref "C33") (pin "2") (pinfunction "2_2") (pintype "passive"))
      (node (ref "C34") (pin "1") (pinfunction "1_1") (pintype "passive"))
      (node (ref "R36") (pin "1") (pinfunction "1_1") (pintype "passive"))
    )
    (net (code "62") (name "Net-(C35-Pad1)") (class "Default")
      (node (ref "C35") (pin "1") (pinfunction "1_1") (pintype "passive"))
      (node (ref "R30") (pin "1") (pinfunction "1_1") (pintype "passive"))
    )
    (net (code "63") (name "Net-(C39-Pad1)") (class "Default")
      (node (ref "C39") (pin "1") (pinfunction "1_1") (pintype "passive"))
      (node (ref "R43") (pin "2") (pinfunction "2_2") (pintype "passive"))
    )
    (net (code "64") (name "Net-(C39-Pad2)") (class "Default")
      (node (ref "C39") (pin "2") (pinfunction "2_2") (pintype "passive"))
      (node (ref "R26") (pin "2") (pinfunction "2_2") (pintype "passive"))
    )
    (net (code "65") (name "Net-(C41-Pad2)") (class "Default")
      (node (ref "C41") (pin "2") (pinfunction "2_2") (pintype "passive"))
      (node (ref "JP4") (pin "3") (pinfunction "3_3") (pintype "passive"))
    )
    (net (code "66") (name "Net-(C43-Pad2)") (class "Default")
      (node (ref "C43") (pin "2") (pinfunction "2_2") (pintype "passive"))
      (node (ref "R45") (pin "1") (pinfunction "1_1") (pintype "passive"))
    )
    (net (code "67") (name "Net-(C44-Pad2)") (class "Default")
      (node (ref "C44") (pin "2") (pinfunction "2_2") (pintype "passive"))
      (node (ref "R48") (pin "1") (pinfunction "1_1") (pintype "passive"))
    )
    (net (code "68") (name "Net-(C45-Pad1)") (class "Default")
      (node (ref "C45") (pin "1") (pinfunction "1_1") (pintype "passive"))
      (node (ref "R82") (pin "2") (pinfunction "2_2") (pintype "passive"))
    )
    (net (code "69") (name "Net-(C47-Pad2)") (class "Default")
      (node (ref "C47") (pin "2") (pinfunction "2_2") (pintype "passive"))
      (node (ref "R51") (pin "1") (pinfunction "1_1") (pintype "passive"))
    )
    (net (code "70") (name "Net-(C48-Pad2)") (class "Default")
      (node (ref "C48") (pin "2") (pinfunction "2_2") (pintype "passive"))
      (node (ref "R56") (pin "1") (pinfunction "1_1") (pintype "passive"))
    )
    (net (code "71") (name "Net-(C50-Pad2)") (class "Default")
      (node (ref "C50") (pin "2") (pinfunction "2_2") (pintype "passive"))
      (node (ref "R59") (pin "1") (pinfunction "1_1") (pintype "passive"))
    )
    (net (code "72") (name "Net-(C51-Pad2)") (class "Default")
      (node (ref "C51") (pin "2") (pinfunction "2_2") (pintype "passive"))
      (node (ref "R60") (pin "1") (pinfunction "1_1") (pintype "passive"))
    )
    (net (code "73") (name "Net-(C52-Pad1)") (class "Default")
      (node (ref "C52") (pin "1") (pinfunction "1_1") (pintype "passive"))
      (node (ref "R83") (pin "2") (pinfunction "2_2") (pintype "passive"))
    )
    (net (code "74") (name "Net-(C58-Pad2)") (class "Default")
      (node (ref "C58") (pin "2") (pinfunction "2_2") (pintype "passive"))
      (node (ref "R63") (pin "3") (pinfunction "3_3") (pintype "passive"))
      (node (ref "R66") (pin "3") (pinfunction "3_3") (pintype "passive"))
    )
    (net (code "75") (name "Net-(C59-Pad1)") (class "Default")
      (node (ref "C59") (pin "1") (pinfunction "1_1") (pintype "passive"))
      (node (ref "C60") (pin "1") (pinfunction "1_1") (pintype "passive"))
      (node (ref "R65") (pin "1") (pinfunction "1_1") (pintype "passive"))
      (node (ref "R67") (pin "1") (pinfunction "1_1") (pintype "passive"))
      (node (ref "TP8") (pin "TP") (pinfunction "TP_TP") (pintype "passive"))
    )
    (net (code "76") (name "Net-(C61-Pad1)") (class "Default")
      (node (ref "C61") (pin "1") (pinfunction "1_1") (pintype "passive"))
      (node (ref "R68") (pin "2") (pinfunction "2_2") (pintype "passive"))
    )
    (net (code "77") (name "Net-(C61-Pad2)") (class "Default")
      (node (ref "C61") (pin "2") (pinfunction "2_2") (pintype "passive"))
      (node (ref "C62") (pin "1") (pinfunction "1_1") (pintype "passive"))
      (node (ref "R71") (pin "3") (pinfunction "3_3") (pintype "passive"))
    )
    (net (code "78") (name "Net-(C64-Pad2)") (class "Default")
      (node (ref "C64") (pin "2") (pinfunction "2_2") (pintype "passive"))
      (node (ref "R75") (pin "3") (pinfunction "3_3") (pintype "passive"))
    )
    (net (code "79") (name "Net-(C80-Pad1)") (class "Default")
      (node (ref "C80") (pin "1") (pinfunction "1_1") (pintype "passive"))
      (node (ref "L1") (pin "3") (pinfunction "3_3") (pintype "passive"))
      (node (ref "PF1") (pin "1") (pinfunction "1_1") (pintype "passive"))
    )
    (net (code "80") (name "Net-(D11-C)") (class "Default")
      (node (ref "D11") (pin "K") (pinfunction "C_K") (pintype "passive"))
      (node (ref "Q1") (pin "3") (pinfunction "C_3") (pintype "passive"))
    )
    (net (code "81") (name "Net-(D11-PadA)") (class "Default")
      (node (ref "D11") (pin "A") (pinfunction "A_A") (pintype "passive"))
      (node (ref "R7") (pin "2") (pinfunction "2_2") (pintype "passive"))
    )
    (net (code "82") (name "Net-(J1-VEE)") (class "Default")
      (node (ref "J1") (pin "3") (pinfunction "VEE_3") (pintype "power_in"))
      (node (ref "R2") (pin "2") (pinfunction "2_2") (pintype "passive"))
    )
    (net (code "83") (name "Net-(JP2-Pad1)") (class "Default")
      (node (ref "JP2") (pin "1") (pinfunction "1_1") (pintype "passive"))
      (node (ref "R1") (pin "1") (pinfunction "1_1") (pintype "passive"))
    )
    (net (code "84") (name "Net-(JP2-Pad3)") (class "Default")
      (node (ref "JP2") (pin "3") (pinfunction "3_3") (pintype "passive"))
      (node (ref "R4") (pin "1") (pinfunction "1_1") (pintype "passive"))
    )
    (net (code "85") (name "Net-(JP2-Pad4)") (class "Default")
      (node (ref "JP2") (pin "4") (pinfunction "4_4") (pintype "passive"))
      (node (ref "R3") (pin "1") (pinfunction "1_1") (pintype "passive"))
    )
    (net (code "86") (name "Net-(JP4-Pad1)") (class "Default")
      (node (ref "JP4") (pin "1") (pinfunction "1_1") (pintype "passive"))
      (node (ref "R42") (pin "2") (pinfunction "2_2") (pintype "passive"))
    )
    (net (code "87") (name "Net-(JP5-Pad2)") (class "Default")
      (node (ref "JP5") (pin "2") (pinfunction "2_2") (pintype "passive"))
      (node (ref "R12") (pin "2") (pinfunction "2_2") (pintype "passive"))
    )
    (net (code "88") (name "Net-(JP5-Pad4)") (class "Default")
      (node (ref "JP5") (pin "4") (pinfunction "4_4") (pintype "passive"))
      (node (ref "R14") (pin "2") (pinfunction "2_2") (pintype "passive"))
    )
    (net (code "89") (name "Net-(Q1-B)") (class "Default")
      (node (ref "Q1") (pin "1") (pinfunction "B_1") (pintype "passive"))
      (node (ref "R8") (pin "2") (pinfunction "2_2") (pintype "passive"))
    )
    (net (code "90") (name "Net-(Q2-D)") (class "Default")
      (node (ref "Q2") (pin "2") (pinfunction "D_2") (pintype "passive"))
      (node (ref "Q2") (pin "4") (pinfunction "D2_4") (pintype "passive"))
      (node (ref "X5") (pin "2") (pinfunction "2_2") (pintype "passive"))
    )
    (net (code "91") (name "Net-(Q2-G)") (class "Default")
      (node (ref "Q2") (pin "1") (pinfunction "G_1") (pintype "passive"))
      (node (ref "R9") (pin "2") (pinfunction "2_2") (pintype "passive"))
    )
    (net (code "92") (name "Net-(Q3-G)") (class "Default")
      (node (ref "Q3") (pin "1") (pinfunction "G_1") (pintype "passive"))
      (node (ref "R15") (pin "2") (pinfunction "2_2") (pintype "passive"))
    )
    (net (code "93") (name "Net-(Q4-G)") (class "Default")
      (node (ref "Q4") (pin "1") (pinfunction "G_1") (pintype "passive"))
      (node (ref "R17") (pin "2") (pinfunction "2_2") (pintype "passive"))
    )
    (net (code "94") (name "Net-(Q5-B)") (class "Default")
      (node (ref "D2") (pin "C") (pinfunction "C_C") (pintype "passive"))
      (node (ref "Q5") (pin "1") (pinfunction "B_1") (pintype "passive"))
      (node (ref "R19") (pin "1") (pinfunction "1_1") (pintype "passive"))
    )
    (net (code "95") (name "Net-(R6-Pad2)") (class "Default")
      (node (ref "R6") (pin "2") (pinfunction "2_2") (pintype "passive"))
      (node (ref "X5") (pin "1") (pinfunction "1_1") (pintype "passive"))
    )
    (net (code "96") (name "Net-(R52-Pad2)") (class "Default")
      (node (ref "R52") (pin "2") (pinfunction "2_2") (pintype "passive"))
      (node (ref "R52") (pin "3") (pinfunction "3_3") (pintype "passive"))
      (node (ref "R53") (pin "1") (pinfunction "1_1") (pintype "passive"))
    )
    (net (code "97") (name "Net-(R63-Pad2)") (class "Default")
      (node (ref "R63") (pin "2") (pinfunction "2_2") (pintype "passive"))
      (node (ref "R64") (pin "1") (pinfunction "1_1") (pintype "passive"))
    )
    (net (code "98") (name "Net-(R65-Pad2)") (class "Default")
      (node (ref "R65") (pin "2") (pinfunction "2_2") (pintype "passive"))
      (node (ref "R66") (pin "2") (pinfunction "2_2") (pintype "passive"))
    )
    (net (code "99") (name "Net-(R71-Pad2)") (class "Default")
      (node (ref "R71") (pin "2") (pinfunction "2_2") (pintype "passive"))
      (node (ref "R72") (pin "2") (pinfunction "2_2") (pintype "passive"))
    )
    (net (code "100") (name "Net-(R75-Pad2)") (class "Default")
      (node (ref "R75") (pin "2") (pinfunction "2_2") (pintype "passive"))
      (node (ref "R76") (pin "1") (pinfunction "1_1") (pintype "passive"))
    )
    (net (code "101") (name "Net-(S1-O)") (class "Default")
      (node (ref "C23") (pin "1") (pinfunction "1_1") (pintype "passive"))
      (node (ref "L4") (pin "1") (pinfunction "1_1") (pintype "passive"))
      (node (ref "S1") (pin "3") (pinfunction "O_3") (pintype "passive"))
    )
    (net (code "102") (name "Net-(S1-P)") (class "Default")
      (node (ref "PF1") (pin "2") (pinfunction "2_2") (pintype "passive"))
      (node (ref "S1") (pin "2") (pinfunction "P_2") (pintype "passive"))
    )
    (net (code "103") (name "Net-(U1-VBAT)") (class "Default")
      (node (ref "B1") (pin "+") (pinfunction "+_+") (pintype "passive"))
      (node (ref "U1") (pin "3") (pinfunction "VBAT_3") (pintype "power_in"))
    )
    (net (code "104") (name "Net-(U1-X1)") (class "Default")
      (node (ref "U1") (pin "1") (pinfunction "X1_1") (pintype "passive"))
      (node (ref "Y4") (pin "2") (pinfunction "2_2") (pintype "passive"))
    )
    (net (code "105") (name "Net-(U1-X2)") (class "Default")
      (node (ref "U1") (pin "2") (pinfunction "X2_2") (pintype "passive"))
      (node (ref "Y4") (pin "1") (pinfunction "1_1") (pintype "passive"))
    )
    (net (code "106") (name "Net-(U2-AREF)") (class "Default")
      (node (ref "C8") (pin "1") (pinfunction "1_1") (pintype "passive"))
      (node (ref "U2") (pin "62") (pinfunction "AREF_62") (pintype "bidirectional"))
    )
    (net (code "107") (name "Net-(U2-XTAL1)") (class "Default")
      (node (ref "C7") (pin "1") (pinfunction "1_1") (pintype "passive"))
      (node (ref "U2") (pin "24") (pinfunction "XTAL1_24") (pintype "bidirectional"))
      (node (ref "Y1") (pin "1") (pinfunction "1_1") (pintype "passive"))
    )
    (net (code "108") (name "Net-(U2-XTAL2)") (class "Default")
      (node (ref "C6") (pin "1") (pinfunction "1_1") (pintype "passive"))
      (node (ref "U2") (pin "23") (pinfunction "XTAL2_23") (pintype "bidirectional"))
      (node (ref "Y1") (pin "2") (pinfunction "2_2") (pintype "passive"))
    )
    (net (code "109") (name "Net-(U3A-C1+)") (class "Default")
      (node (ref "C10") (pin "1") (pinfunction "1_1") (pintype "passive"))
      (node (ref "U3") (pin "28") (pinfunction "C1+_28") (pintype "passive"))
    )
    (net (code "110") (name "Net-(U3A-C1-)") (class "Default")
      (node (ref "C10") (pin "2") (pinfunction "2_2") (pintype "passive"))
      (node (ref "U3") (pin "24") (pinfunction "C1-_24") (pintype "passive"))
    )
    (net (code "111") (name "Net-(U3A-C2+)") (class "Default")
      (node (ref "C13") (pin "1") (pinfunction "1_1") (pintype "passive"))
      (node (ref "U3") (pin "1") (pinfunction "C2+_1") (pintype "passive"))
    )
    (net (code "112") (name "Net-(U3A-C2-)") (class "Default")
      (node (ref "C13") (pin "2") (pinfunction "2_2") (pintype "passive"))
      (node (ref "U3") (pin "2") (pinfunction "C2-_2") (pintype "passive"))
    )
    (net (code "113") (name "Net-(U3A-V+)") (class "Default")
      (node (ref "C11") (pin "2") (pinfunction "2_2") (pintype "passive"))
      (node (ref "U3") (pin "27") (pinfunction "V+_27") (pintype "passive"))
    )
    (net (code "114") (name "Net-(U3A-V-)") (class "Default")
      (node (ref "C12") (pin "2") (pinfunction "2_2") (pintype "passive"))
      (node (ref "U3") (pin "3") (pinfunction "V-_3") (pintype "passive"))
    )
    (net (code "115") (name "Net-(U5A--IN)") (class "Default")
      (node (ref "C29") (pin "1") (pinfunction "1_1") (pintype "passive"))
      (node (ref "R25") (pin "1") (pinfunction "1_1") (pintype "passive"))
      (node (ref "R28") (pin "2") (pinfunction "2_2") (pintype "passive"))
      (node (ref "U5") (pin "2") (pinfunction "-IN_2") (pintype "input"))
    )
    (net (code "116") (name "Net-(U5A-OUT)") (class "Default")
      (node (ref "C29") (pin "2") (pinfunction "2_2") (pintype "passive"))
      (node (ref "C32") (pin "1") (pinfunction "1_1") (pintype "passive"))
      (node (ref "R25") (pin "2") (pinfunction "2_2") (pintype "passive"))
      (node (ref "U5") (pin "1") (pinfunction "OUT_1") (pintype "output"))
    )
    (net (code "117") (name "Net-(U5B-+IN)") (class "Default")
      (node (ref "C34") (pin "2") (pinfunction "2_2") (pintype "passive"))
      (node (ref "R24") (pin "2") (pinfunction "2_2") (pintype "passive"))
      (node (ref "U5") (pin "5") (pinfunction "+IN_5") (pintype "input"))
    )
    (net (code "118") (name "Net-(U5B--IN)") (class "Default")
      (node (ref "R30") (pin "2") (pinfunction "2_2") (pintype "passive"))
      (node (ref "R36") (pin "2") (pinfunction "2_2") (pintype "passive"))
      (node (ref "U5") (pin "6") (pinfunction "-IN_6") (pintype "input"))
      (node (ref "U5") (pin "7") (pinfunction "OUT_7") (pintype "output"))
    )
    (net (code "119") (name "Net-(U5C-+IN)") (class "Default")
      (node (ref "C35") (pin "2") (pinfunction "2_2") (pintype "passive"))
      (node (ref "C36") (pin "1") (pinfunction "1_1") (pintype "passive"))
      (node (ref "R38") (pin "1") (pinfunction "1_1") (pintype "passive"))
      (node (ref "U5") (pin "10") (pinfunction "+IN_10") (pintype "input"))
    )
    (net (code "120") (name "Net-(U5C--IN)") (class "Default")
      (node (ref "C36") (pin "2") (pinfunction "2_2") (pintype "passive"))
      (node (ref "R34") (pin "2") (pinfunction "2_2") (pintype "passive"))
      (node (ref "R39") (pin "1") (pinfunction "1_1") (pintype "passive"))
      (node (ref "U5") (pin "9") (pinfunction "-IN_9") (pintype "input"))
    )
    (net (code "121") (name "Net-(U5C-OUT)") (class "Default")
      (node (ref "R29") (pin "2") (pinfunction "2_2") (pintype "passive"))
      (node (ref "R34") (pin "1") (pinfunction "1_1") (pintype "passive"))
      (node (ref "U5") (pin "8") (pinfunction "OUT_8") (pintype "output"))
    )
    (net (code "122") (name "Net-(U5D-+IN)") (class "Default")
      (node (ref "C37") (pin "1") (pinfunction "1_1") (pintype "passive"))
      (node (ref "C38") (pin "2") (pinfunction "2_2") (pintype "passive"))
      (node (ref "R29") (pin "1") (pinfunction "1_1") (pintype "passive"))
      (node (ref "U5") (pin "12") (pinfunction "+IN_12") (pintype "input"))
    )
    (net (code "123") (name "Net-(U5D--IN)") (class "Default")
      (node (ref "C37") (pin "2") (pinfunction "2_2") (pintype "passive"))
      (node (ref "R35") (pin "2") (pinfunction "2_2") (pintype "passive"))
      (node (ref "R40") (pin "1") (pinfunction "1_1") (pintype "passive"))
      (node (ref "U5") (pin "13") (pinfunction "-IN_13") (pintype "input"))
    )
    (net (code "124") (name "Net-(U5D-OUT)") (class "Default")
      (node (ref "R31") (pin "2") (pinfunction "2_2") (pintype "passive"))
      (node (ref "R35") (pin "1") (pinfunction "1_1") (pintype "passive"))
      (node (ref "U5") (pin "14") (pinfunction "OUT_14") (pintype "output"))
    )
    (net (code "125") (name "Net-(U6A-EST)") (class "Default")
      (node (ref "R32") (pin "1") (pinfunction "1_1") (pintype "passive"))
      (node (ref "U6") (pin "16") (pinfunction "EST_16") (pintype "input"))
    )
    (net (code "126") (name "Net-(U6A-GS)") (class "Default")
      (node (ref "C40") (pin "1") (pinfunction "1_1") (pintype "passive"))
      (node (ref "R41") (pin "1") (pinfunction "1_1") (pintype "passive"))
      (node (ref "U6") (pin "3") (pinfunction "GS_3") (pintype "input"))
    )
    (net (code "127") (name "Net-(U6A-IN+)") (class "Default")
      (node (ref "U6") (pin "1") (pinfunction "IN+_1") (pintype "input"))
      (node (ref "U6") (pin "4") (pinfunction "VREF_4") (pintype "output"))
    )
    (net (code "128") (name "Net-(U6A-IN-)") (class "Default")
      (node (ref "C40") (pin "2") (pinfunction "2_2") (pintype "passive"))
      (node (ref "R41") (pin "2") (pinfunction "2_2") (pintype "passive"))
      (node (ref "R45") (pin "2") (pinfunction "2_2") (pintype "passive"))
      (node (ref "U6") (pin "2") (pinfunction "IN-_2") (pintype "input"))
    )
    (net (code "129") (name "Net-(U6A-OSC1)") (class "Default")
      (node (ref "U6") (pin "7") (pinfunction "OSC1_7") (pintype "input"))
      (node (ref "Y2") (pin "2") (pinfunction "2_2") (pintype "passive"))
    )
    (net (code "130") (name "Net-(U6A-OSC2)") (class "Default")
      (node (ref "U6") (pin "8") (pinfunction "OSC2_8") (pintype "bidirectional"))
      (node (ref "Y2") (pin "1") (pinfunction "1_1") (pintype "passive"))
    )
    (net (code "131") (name "Net-(U6A-ST{slash}GT)") (class "Default")
      (node (ref "C30") (pin "1") (pinfunction "1_1") (pintype "passive"))
      (node (ref "R32") (pin "2") (pinfunction "2_2") (pintype "passive"))
      (node (ref "U6") (pin "17") (pinfunction "ST/GT_17") (pintype "bidirectional"))
    )
    (net (code "132") (name "Net-(U7A-COM)") (class "Default")
      (node (ref "C44") (pin "1") (pinfunction "1_1") (pintype "passive"))
      (node (ref "R46") (pin "1") (pinfunction "1_1") (pintype "passive"))
      (node (ref "U7") (pin "2") (pinfunction "COM_2") (pintype "passive"))
    )
    (net (code "133") (name "Net-(U7B-COM)") (class "Default")
      (node (ref "C58") (pin "1") (pinfunction "1_1") (pintype "passive"))
      (node (ref "R62") (pin "1") (pinfunction "1_1") (pintype "passive"))
      (node (ref "U7") (pin "6") (pinfunction "COM_6") (pintype "passive"))
    )
    (net (code "134") (name "Net-(U8A-A{slash}D_CAP1)") (class "Default")
      (node (ref "C55") (pin "+") (pinfunction "+_+") (pintype "passive"))
      (node (ref "U8") (pin "10") (pinfunction "A/D_CAP1_10") (pintype "output"))
    )
    (net (code "135") (name "Net-(U8A-A{slash}D_CAP2)") (class "Default")
      (node (ref "C56") (pin "+") (pinfunction "+_+") (pintype "passive"))
      (node (ref "U8") (pin "11") (pinfunction "A/D_CAP2_11") (pintype "output"))
    )
    (net (code "136") (name "Net-(U8A-RX_AMP_IN)") (class "Default")
      (node (ref "C46") (pin "2") (pinfunction "2_2") (pintype "passive"))
      (node (ref "JP4") (pin "2") (pinfunction "2_2") (pintype "passive"))
      (node (ref "R43") (pin "1") (pinfunction "1_1") (pintype "passive"))
      (node (ref "R47") (pin "2") (pinfunction "2_2") (pintype "passive"))
      (node (ref "U8") (pin "14") (pinfunction "RX_AMP_IN_14") (pintype "input"))
    )
    (net (code "137") (name "Net-(U8A-RX_AMP_OUT)") (class "Default")
      (node (ref "C41") (pin "1") (pinfunction "1_1") (pintype "passive"))
      (node (ref "C46") (pin "1") (pinfunction "1_1") (pintype "passive"))
      (node (ref "R42") (pin "1") (pinfunction "1_1") (pintype "passive"))
      (node (ref "R47") (pin "1") (pinfunction "1_1") (pintype "passive"))
      (node (ref "U8") (pin "15") (pinfunction "RX_AMP_OUT_15") (pintype "output"))
    )
    (net (code "138") (name "Net-(U8A-SUM_IN)") (class "Default")
      (node (ref "C49") (pin "1") (pinfunction "1_1") (pintype "passive"))
      (node (ref "R54") (pin "1") (pinfunction "1_1") (pintype "passive"))
      (node (ref "R57") (pin "2") (pinfunction "2_2") (pintype "passive"))
      (node (ref "R58") (pin "2") (pinfunction "2_2") (pintype "passive"))
      (node (ref "U8") (pin "18") (pinfunction "SUM_IN_18") (pintype "input"))
    )
    (net (code "139") (name "Net-(U8A-SUM_OUT)") (class "Default")
      (node (ref "C49") (pin "2") (pinfunction "2_2") (pintype "passive"))
      (node (ref "R54") (pin "2") (pinfunction "2_2") (pintype "passive"))
      (node (ref "U8") (pin "19") (pinfunction "SUM_OUT_19") (pintype "output"))
    )
    (net (code "140") (name "Net-(U8A-TX_AUD_OUT)") (class "Default")
      (node (ref "R57") (pin "1") (pinfunction "1_1") (pintype "passive"))
      (node (ref "U8") (pin "17") (pinfunction "TX_AUD_OUT_17") (pintype "output"))
    )
    (net (code "141") (name "Net-(U8A-TX_SUB_AUD_OUT)") (class "Default")
      (node (ref "R58") (pin "1") (pinfunction "1_1") (pintype "passive"))
      (node (ref "U8") (pin "21") (pinfunction "TX_SUB_AUD_OUT_21") (pintype "output"))
    )
    (net (code "142") (name "Net-(U8A-VBIAS)") (class "Default")
      (node (ref "C57") (pin "1") (pinfunction "1_1") (pintype "passive"))
      (node (ref "U8") (pin "13") (pinfunction "VBIAS_13") (pintype "input"))
    )
    (net (code "143") (name "Net-(U8A-XTAL)") (class "Default")
      (node (ref "C54") (pin "1") (pinfunction "1_1") (pintype "passive"))
      (node (ref "R55") (pin "1") (pinfunction "1_1") (pintype "passive"))
      (node (ref "U8") (pin "1") (pinfunction "XTAL_1") (pintype "output"))
      (node (ref "Y3") (pin "2") (pinfunction "2_2") (pintype "passive"))
    )
    (net (code "144") (name "Net-(U8A-XTAL{slash}CLOCK)") (class "Default")
      (node (ref "C53") (pin "1") (pinfunction "1_1") (pintype "passive"))
      (node (ref "R55") (pin "2") (pinfunction "2_2") (pintype "passive"))
      (node (ref "U8") (pin "2") (pinfunction "XTAL/CLOCK_2") (pintype "input"))
      (node (ref "Y3") (pin "1") (pinfunction "1_1") (pintype "passive"))
    )
    (net (code "145") (name "Net-(U9-AM_CAP)") (class "Default")
      (node (ref "C67") (pin "+") (pinfunction "+_+") (pintype "passive"))
      (node (ref "U9") (pin "14") (pinfunction "AM_CAP_14") (pintype "output"))
    )
    (net (code "146") (name "Net-(U9-ANA_IN+)") (class "Default")
      (node (ref "C59") (pin "2") (pinfunction "2_2") (pintype "passive"))
      (node (ref "U9") (pin "17") (pinfunction "ANA_IN+_17") (pintype "input"))
    )
    (net (code "147") (name "Net-(U9-ANA_IN-)") (class "Default")
      (node (ref "C63") (pin "2") (pinfunction "2_2") (pintype "passive"))
      (node (ref "U9") (pin "16") (pinfunction "ANA_IN-_16") (pintype "input"))
    )
    (net (code "148") (name "Net-(U9-AUD_OUT)") (class "Default")
      (node (ref "C64") (pin "1") (pinfunction "1_1") (pintype "passive"))
      (node (ref "U9") (pin "13") (pinfunction "AUD_OUT_13") (pintype "output"))
    )
    (net (code "149") (name "Net-(U10A-+IN)") (class "Default")
      (node (ref "C66") (pin "1") (pinfunction "1_1") (pintype "passive"))
      (node (ref "R74") (pin "1") (pinfunction "1_1") (pintype "passive"))
      (node (ref "R78") (pin "2") (pinfunction "2_2") (pintype "passive"))
      (node (ref "U10") (pin "3") (pinfunction "+IN_3") (pintype "input"))
    )
    (net (code "150") (name "Net-(U10B--IN)") (class "Default")
      (node (ref "C48") (pin "1") (pinfunction "1_1") (pintype "passive"))
      (node (ref "R52") (pin "1") (pinfunction "1_1") (pintype "passive"))
      (node (ref "R60") (pin "2") (pinfunction "2_2") (pintype "passive"))
      (node (ref "U10") (pin "6") (pinfunction "-IN_6") (pintype "input"))
    )
    (net (code "151") (name "Net-(U10B-OUT)") (class "Default")
      (node (ref "R53") (pin "2") (pinfunction "2_2") (pintype "passive"))
      (node (ref "R56") (pin "2") (pinfunction "2_2") (pintype "passive"))
      (node (ref "R83") (pin "1") (pinfunction "1_1") (pintype "passive"))
      (node (ref "U10") (pin "7") (pinfunction "OUT_7") (pintype "output"))
    )
    (net (code "152") (name "Net-(U10C--IN)") (class "Default")
      (node (ref "C42") (pin "1") (pinfunction "1_1") (pintype "passive"))
      (node (ref "R44") (pin "1") (pinfunction "1_1") (pintype "passive"))
      (node (ref "R48") (pin "2") (pinfunction "2_2") (pintype "passive"))
      (node (ref "U10") (pin "9") (pinfunction "-IN_9") (pintype "input"))
    )
    (net (code "153") (name "Net-(U10C-OUT)") (class "Default")
      (node (ref "C42") (pin "2") (pinfunction "2_2") (pintype "passive"))
      (node (ref "R44") (pin "2") (pinfunction "2_2") (pintype "passive"))
      (node (ref "R82") (pin "1") (pinfunction "1_1") (pintype "passive"))
      (node (ref "U10") (pin "8") (pinfunction "OUT_8") (pintype "output"))
    )
    (net (code "154") (name "Net-(U10D-+IN)") (class "Default")
      (node (ref "C65") (pin "1") (pinfunction "1_1") (pintype "passive"))
      (node (ref "R73") (pin "1") (pinfunction "1_1") (pintype "passive"))
      (node (ref "R77") (pin "2") (pinfunction "2_2") (pintype "passive"))
      (node (ref "U10") (pin "12") (pinfunction "+IN_12") (pintype "input"))
    )
    (net (code "155") (name "Net-(U12-IN)") (class "Default")
      (node (ref "C3") (pin "+") (pinfunction "+_+") (pintype "passive"))
      (node (ref "C79") (pin "+") (pinfunction "+_+") (pintype "passive"))
      (node (ref "L2") (pin "1") (pinfunction "1_1") (pintype "passive"))
      (node (ref "L3") (pin "1") (pinfunction "1_1") (pintype "passive"))
      (node (ref "U12") (pin "3") (pinfunction "IN_3") (pintype "input"))
    )
    (net (code "156") (name "Net-(X1A-SK)") (class "Default")
      (node (ref "L1") (pin "1") (pinfunction "1_1") (pintype "passive"))
      (node (ref "X1") (pin "1") (pinfunction "SK_1") (pintype "passive"))
    )
    (net (code "157") (name "Net-(X1B-SK)") (class "Default")
      (node (ref "L1") (pin "2") (pinfunction "2_2") (pintype "passive"))
      (node (ref "X1") (pin "2") (pinfunction "SK_2") (pintype "passive"))
    )
    (net (code "158") (name "PA0") (class "Default")
      (node (ref "J1") (pin "7") (pinfunction "DB0_7") (pintype "passive"))
      (node (ref "U2") (pin "51") (pinfunction "(AD0)PA0_51") (pintype "bidirectional"))
    )
    (net (code "159") (name "PA1") (class "Default")
      (node (ref "J1") (pin "8") (pinfunction "DB1_8") (pintype "passive"))
      (node (ref "U2") (pin "50") (pinfunction "(AD1)PA1_50") (pintype "bidirectional"))
    )
    (net (code "160") (name "PA2") (class "Default")
      (node (ref "J1") (pin "9") (pinfunction "DB2_9") (pintype "passive"))
      (node (ref "U2") (pin "49") (pinfunction "(AD2)PA2_49") (pintype "bidirectional"))
    )
    (net (code "161") (name "PA3") (class "Default")
      (node (ref "J1") (pin "10") (pinfunction "DB3_10") (pintype "passive"))
      (node (ref "U2") (pin "48") (pinfunction "(AD3)PA3_48") (pintype "bidirectional"))
    )
    (net (code "162") (name "PA4") (class "Default")
      (node (ref "J1") (pin "11") (pinfunction "DB4_11") (pintype "passive"))
      (node (ref "U2") (pin "47") (pinfunction "(AD4)PA4_47") (pintype "bidirectional"))
    )
    (net (code "163") (name "PA5") (class "Default")
      (node (ref "J1") (pin "12") (pinfunction "DB5_12") (pintype "passive"))
      (node (ref "U2") (pin "46") (pinfunction "(AD5)PA5_46") (pintype "bidirectional"))
    )
    (net (code "164") (name "PA6") (class "Default")
      (node (ref "J1") (pin "13") (pinfunction "DB6_13") (pintype "passive"))
      (node (ref "U2") (pin "45") (pinfunction "(AD6)PA6_45") (pintype "bidirectional"))
    )
    (net (code "165") (name "PA7") (class "Default")
      (node (ref "J1") (pin "14") (pinfunction "DB7_14") (pintype "passive"))
      (node (ref "U2") (pin "44") (pinfunction "(AD7)PA7_44") (pintype "bidirectional"))
    )
    (net (code "166") (name "PTT") (class "Default")
      (node (ref "Q3") (pin "2") (pinfunction "D_2") (pintype "passive"))
      (node (ref "X3") (pin "1") (pinfunction "1_1") (pintype "passive"))
      (node (ref "X4") (pin "1") (pinfunction "1_1") (pintype "passive"))
    )
    (net (code "167") (name "PTT_DRIVE") (class "Default")
      (node (ref "R15") (pin "1") (pinfunction "1_1") (pintype "passive"))
      (node (ref "U2") (pin "36") (pinfunction "(A9)PC1_36") (pintype "output"))
    )
    (net (code "168") (name "RESET") (class "Default")
      (node (ref "C5") (pin "1") (pinfunction "1_1") (pintype "passive"))
      (node (ref "D1") (pin "A") (pinfunction "A_A") (pintype "passive"))
      (node (ref "JP1") (pin "6") (pinfunction "6_6") (pintype "passive"))
      (node (ref "JP2") (pin "5") (pinfunction "5_5") (pintype "passive"))
      (node (ref "R5") (pin "1") (pinfunction "1_1") (pintype "passive"))
      (node (ref "U2") (pin "20") (pinfunction "~{RESET}_20") (pintype "input"))
    )
    (net (code "169") (name "RX_AUDIO_OUT") (class "Default")
      (node (ref "C43") (pin "1") (pinfunction "1_1") (pintype "passive"))
      (node (ref "J2") (pin "1") (pinfunction "1_1") (pintype "passive"))
      (node (ref "TP6") (pin "TP") (pinfunction "TP_TP") (pintype "input"))
      (node (ref "U8") (pin "16") (pinfunction "RX_AUD_OUT_16") (pintype "output"))
      (node (ref "U8") (pin "20") (pinfunction "MOD1_IN_20") (pintype "input"))
    )
    (net (code "170") (name "RX_AUDIO_RET") (class "Default")
      (node (ref "J2") (pin "2") (pinfunction "2_2") (pintype "passive"))
      (node (ref "U7") (pin "5") (pinfunction "NO_5") (pintype "passive"))
    )
    (net (code "171") (name "SPI_MISO") (class "Default")
      (node (ref "J2") (pin "14") (pinfunction "14_14") (pintype "passive"))
      (node (ref "U2") (pin "13") (pinfunction "(MISO/PCINT3)PB3_13") (pintype "bidirectional"))
      (node (ref "U8") (pin "5") (pinfunction "REPLY_DATA_5") (pintype "bidirectional"))
      (node (ref "U9") (pin "3") (pinfunction "MISO_3") (pintype "bidirectional"))
    )
    (net (code "172") (name "SPI_MOSI") (class "Default")
      (node (ref "J2") (pin "12") (pinfunction "12_12") (pintype "passive"))
      (node (ref "U2") (pin "12") (pinfunction "(MOSI/PCINT2)PB2_12") (pintype "bidirectional"))
      (node (ref "U8") (pin "4") (pinfunction "COMMAND_DATA_4") (pintype "input"))
      (node (ref "U9") (pin "2") (pinfunction "MOSI_2") (pintype "bidirectional"))
    )
    (net (code "173") (name "SPI_SCK") (class "Default")
      (node (ref "J2") (pin "10") (pinfunction "10_10") (pintype "passive"))
      (node (ref "R4") (pin "2") (pinfunction "2_2") (pintype "passive"))
      (node (ref "U2") (pin "11") (pinfunction "(SCK/PCINT1)PB1_11") (pintype "bidirectional"))
      (node (ref "U8") (pin "3") (pinfunction "SERIAL_CLOCK_3") (pintype "input"))
      (node (ref "U9") (pin "28") (pinfunction "SCLK_28") (pintype "bidirectional"))
    )
    (net (code "174") (name "SPI_SS") (class "Default")
      (node (ref "J2") (pin "16") (pinfunction "16_16") (pintype "passive"))
      (node (ref "U2") (pin "33") (pinfunction "PG0(WR#)_33") (pintype "bidirectional"))
    )
    (net (code "175") (name "SS_ISD") (class "Default")
      (node (ref "U2") (pin "16") (pinfunction "(OC1B/PCINT6)PB6_16") (pintype "bidirectional"))
      (node (ref "U9") (pin "1") (pinfunction "~{SS}_1") (pintype "input"))
    )
    (net (code "176") (name "SS_MX828") (class "Default")
      (node (ref "U2") (pin "10") (pinfunction "~{(SS}/PCINT0)PB0_10") (pintype "bidirectional"))
      (node (ref "U8") (pin "6") (pinfunction "~{CS}_6") (pintype "input"))
    )
    (net (code "177") (name "TCK") (class "Default")
      (node (ref "JP1") (pin "1") (pinfunction "1_1") (pintype "passive"))
      (node (ref "RN1") (pin "1") (pinfunction "1_1") (pintype "passive"))
      (node (ref "U2") (pin "57") (pinfunction "PF4(ADC4/TCK)_57") (pintype "input"))
    )
    (net (code "178") (name "TDI") (class "Default")
      (node (ref "JP1") (pin "9") (pinfunction "9_9") (pintype "passive"))
      (node (ref "R12") (pin "1") (pinfunction "1_1") (pintype "passive"))
      (node (ref "RN1") (pin "4") (pinfunction "4_4") (pintype "passive"))
      (node (ref "U2") (pin "54") (pinfunction "PF7(ADC7/TDI)_54") (pintype "input"))
    )
    (net (code "179") (name "TDO") (class "Default")
      (node (ref "JP1") (pin "3") (pinfunction "3_3") (pintype "passive"))
      (node (ref "R14") (pin "1") (pinfunction "1_1") (pintype "passive"))
      (node (ref "RN1") (pin "3") (pinfunction "3_3") (pintype "passive"))
      (node (ref "U2") (pin "55") (pinfunction "PF6(ADC6/TDO)_55") (pintype "input"))
    )
    (net (code "180") (name "TMS") (class "Default")
      (node (ref "JP1") (pin "5") (pinfunction "5_5") (pintype "passive"))
      (node (ref "RN1") (pin "2") (pinfunction "2_2") (pintype "passive"))
      (node (ref "U2") (pin "56") (pinfunction "PF5(ADC5/TMS)_56") (pintype "input"))
    )
    (net (code "181") (name "TX_AUDIO") (class "Default")
      (node (ref "C52") (pin "2") (pinfunction "2_2") (pintype "passive"))
      (node (ref "J2") (pin "5") (pinfunction "5_5") (pintype "passive"))
      (node (ref "R61") (pin "2") (pinfunction "2_2") (pintype "passive"))
      (node (ref "X3") (pin "7") (pinfunction "7_7") (pintype "passive"))
      (node (ref "X4") (pin "7") (pinfunction "7_7") (pintype "passive"))
    )
    (net (code "182") (name "TX_TONE_OUT") (class "Default")
      (node (ref "C50") (pin "1") (pinfunction "1_1") (pintype "passive"))
      (node (ref "TP5") (pin "TP") (pinfunction "TP_TP") (pintype "input"))
      (node (ref "U8") (pin "23") (pinfunction "MOD2_23") (pintype "output"))
    )
    (net (code "183") (name "VBATT") (class "Default")
      (node (ref "C20") (pin "1") (pinfunction "1_1") (pintype "passive"))
      (node (ref "D7") (pin "C") (pinfunction "C_C") (pintype "passive"))
      (node (ref "R21") (pin "1") (pinfunction "1_1") (pintype "passive"))
      (node (ref "R23") (pin "2") (pinfunction "2_2") (pintype "passive"))
      (node (ref "U2") (pin "59") (pinfunction "PF2(ADC2)_59") (pintype "input"))
    )
    (net (code "184") (name "VREF") (class "Default")
      (node (ref "R24") (pin "1") (pinfunction "1_1") (pintype "passive"))
      (node (ref "U10") (pin "10") (pinfunction "+IN_10") (pintype "input"))
      (node (ref "U10") (pin "13") (pinfunction "-IN_13") (pintype "input"))
      (node (ref "U10") (pin "14") (pinfunction "OUT_14") (pintype "output"))
      (node (ref "U10") (pin "5") (pinfunction "+IN_5") (pintype "input"))
      (node (ref "U5") (pin "3") (pinfunction "+IN_3") (pintype "input"))
    )
    (net (code "185") (name "VSQL") (class "Default")
      (node (ref "C78") (pin "+") (pinfunction "+_+") (pintype "passive"))
      (node (ref "D10") (pin "C") (pinfunction "C_C") (pintype "passive"))
      (node (ref "R31") (pin "1") (pinfunction "1_1") (pintype "passive"))
      (node (ref "R37") (pin "1") (pinfunction "1_1") (pintype "passive"))
      (node (ref "TP3") (pin "TP") (pinfunction "TP_TP") (pintype "input"))
      (node (ref "U2") (pin "61") (pinfunction "PF0(ADC0)_61") (pintype "input"))
      (node (ref "U8") (pin "9") (pinfunction "COMP_IN_9") (pintype "input"))
    )
    (net (code "186") (name "VTEMP") (class "Default")
      (node (ref "C19") (pin "1") (pinfunction "1_1") (pintype "passive"))
      (node (ref "R20") (pin "1") (pinfunction "1_1") (pintype "passive"))
      (node (ref "R22") (pin "2") (pinfunction "2_2") (pintype "passive"))
      (node (ref "U2") (pin "60") (pinfunction "PF1(ADC1)_60") (pintype "input"))
    )
    (net (code "187") (name "XADC") (class "Default")
      (node (ref "J2") (pin "20") (pinfunction "20_20") (pintype "passive"))
      (node (ref "U2") (pin "58") (pinfunction "PF3(ADC3)_58") (pintype "input"))
    )
    (net (code "188") (name "unconnected-(J1-A-Pad15)") (class "Default")
      (node (ref "J1") (pin "15") (pinfunction "A_15") (pintype "passive"))
    )
    (net (code "189") (name "unconnected-(J1-C-Pad16)") (class "Default")
      (node (ref "J1") (pin "16") (pinfunction "C_16") (pintype "passive"))
    )
    (net (code "190") (name "unconnected-(JP1-Pad8)") (class "Default")
      (node (ref "JP1") (pin "8") (pinfunction "8_8") (pintype "passive"))
    )
    (net (code "191") (name "unconnected-(S1-S-Pad1)") (class "Default")
      (node (ref "S1") (pin "1") (pinfunction "S_1") (pintype "passive"))
    )
    (net (code "192") (name "unconnected-(U1-SQW{slash}OUT-Pad7)") (class "Default")
      (node (ref "U1") (pin "7") (pinfunction "SQW/OUT_7") (pintype "output"))
    )
    (net (code "193") (name "unconnected-(U3A-R1OUT-Pad19)") (class "Default")
      (node (ref "U3") (pin "19") (pinfunction "R1OUT_19") (pintype "output"))
    )
    (net (code "194") (name "unconnected-(U3A-R2OUTB-Pad20)") (class "Default")
      (node (ref "U3") (pin "20") (pinfunction "R2OUTB_20") (pintype "output"))
    )
    (net (code "195") (name "unconnected-(U3A-~{INVALID}-Pad21)") (class "Default")
      (node (ref "U3") (pin "21") (pinfunction "~{INVALID}_21") (pintype "output"))
    )
    (net (code "196") (name "unconnected-(U8A-COMP_OUT-Pad8)") (class "Default")
      (node (ref "U8") (pin "8") (pinfunction "COMP_OUT_8") (pintype "output"))
    )
  )
)
